# WP75xx_2_no_usb_v.net
KiCad netlist of a schematic drawn in EAGLE
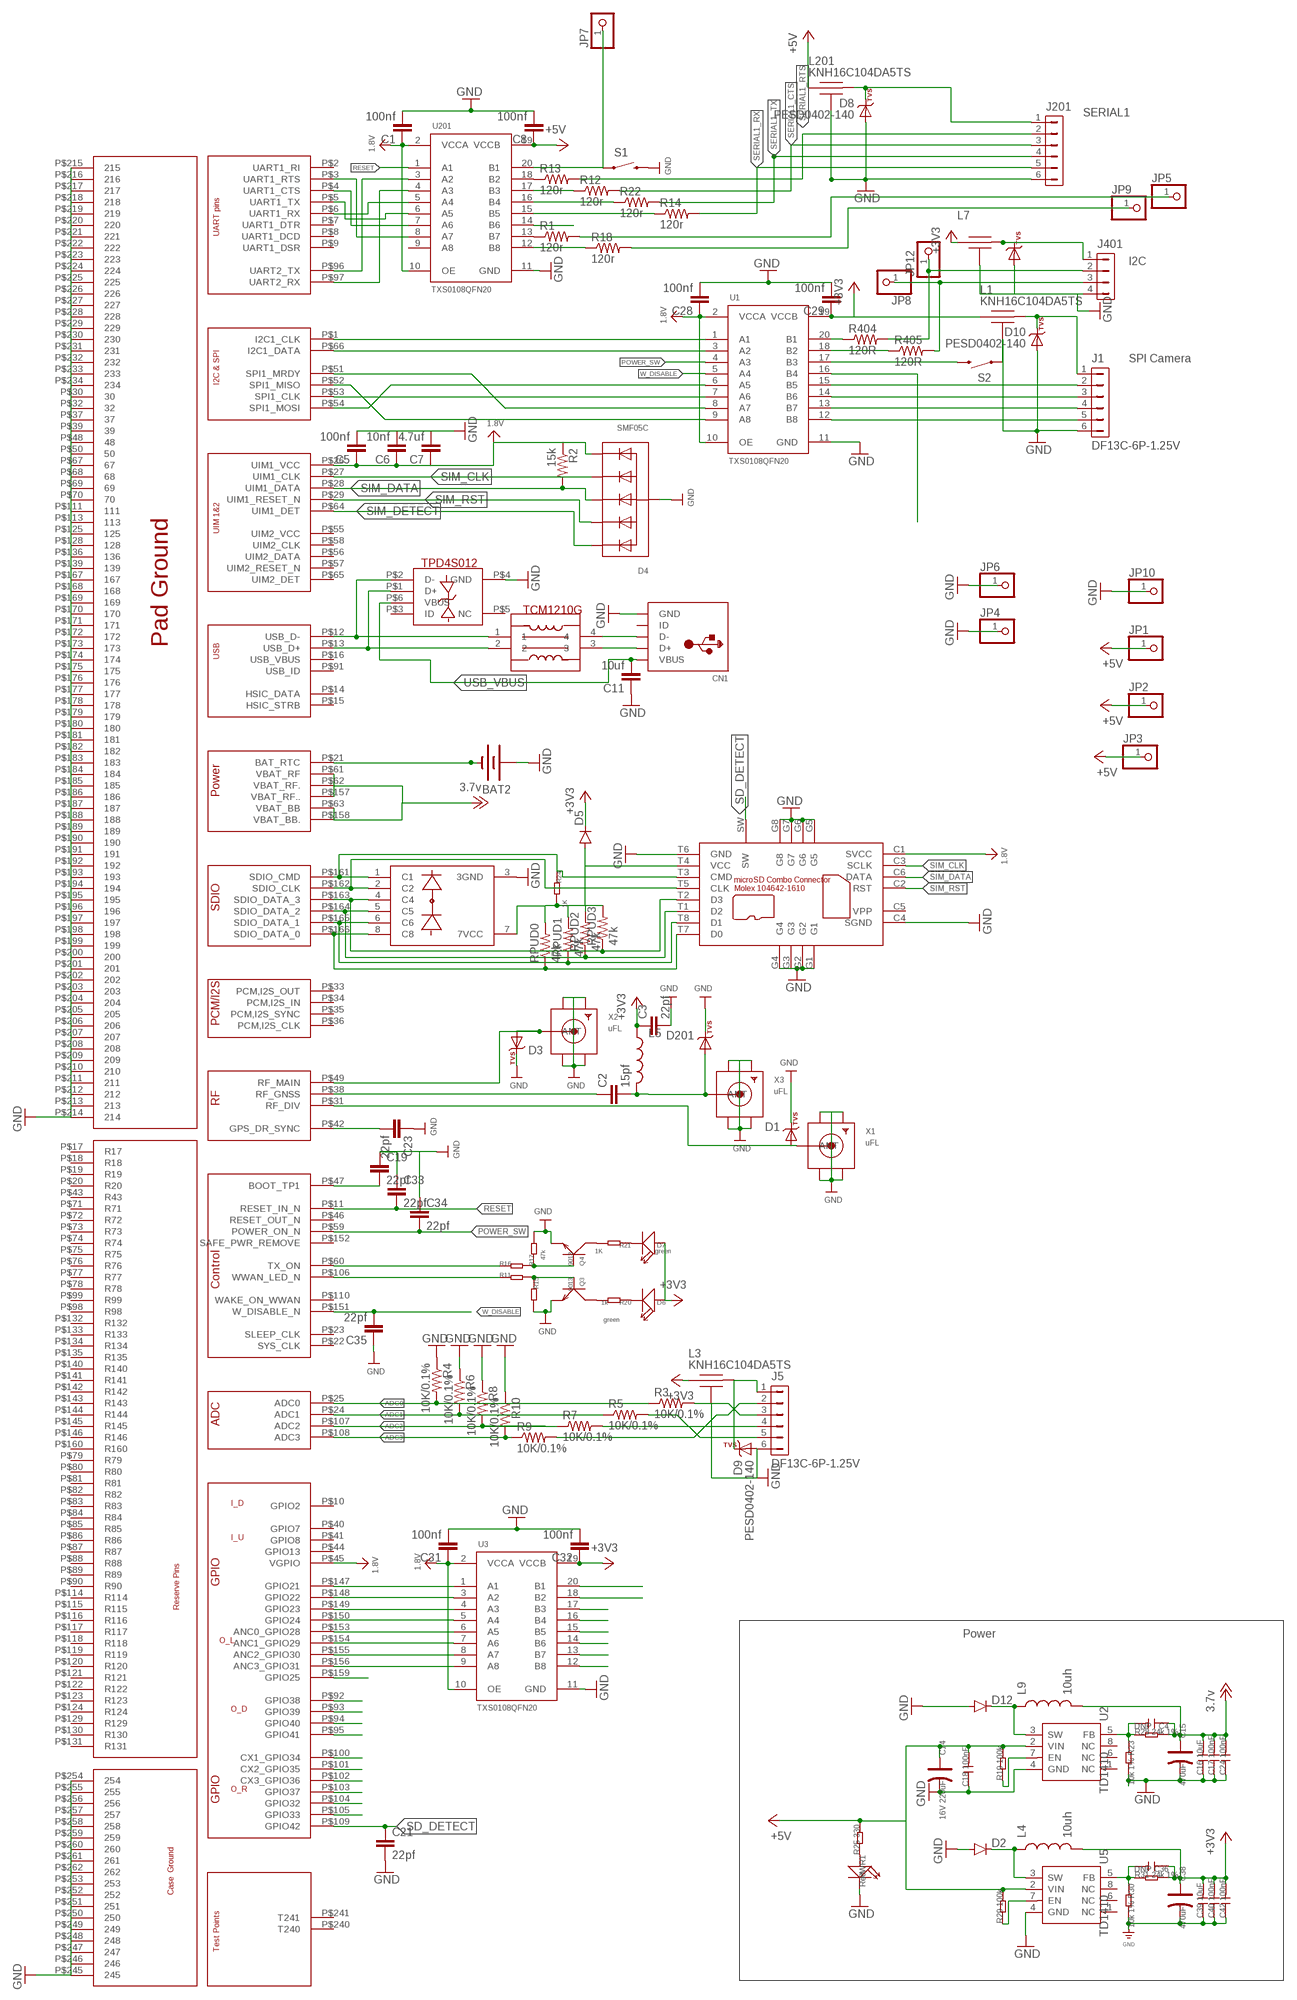
[diagram p0: schematic, sheet 1]

(export (version "E")
  (design (tool "Eeschema 10.0.6"))
  (components
    (comp (ref "BAT2")
      (value "BATTERY12MM")
      (footprint "eagle-import:BATTCON_12MM")
      (libsource (lib "eagle-import") (part "BATTERY12MM"))
    )
    (comp (ref "C1")
      (value "100nf")
      (footprint "eagle-import:0805-CAP")
      (libsource (lib "eagle-import") (part "1.0UF-25V-+80/-20(0805){dblquote}"))
    )
    (comp (ref "C2")
      (value "15pf")
      (footprint "eagle-import:0603-CAP")
      (libsource (lib "eagle-import") (part "0.1UF-25V(+80/-20%)(0603)"))
    )
    (comp (ref "C3")
      (value "22pf")
      (footprint "eagle-import:0603-CAP")
      (libsource (lib "eagle-import") (part "0.1UF-25V(+80/-20%)(0603)"))
    )
    (comp (ref "C4")
      (value "DNP")
      (footprint "eagle-import:C0603")
      (libsource (lib "eagle-import") (part "C-0603"))
    )
    (comp (ref "C5")
      (value "100nf")
      (footprint "eagle-import:0805-CAP")
      (libsource (lib "eagle-import") (part "1.0UF-25V-+80/-20(0805){dblquote}"))
    )
    (comp (ref "C6")
      (value "10nf")
      (footprint "eagle-import:0805-CAP")
      (libsource (lib "eagle-import") (part "1.0UF-25V-+80/-20(0805){dblquote}"))
    )
    (comp (ref "C7")
      (value "4.7uf")
      (footprint "eagle-import:0805-CAP")
      (libsource (lib "eagle-import") (part "1.0UF-25V-+80/-20(0805){dblquote}"))
    )
    (comp (ref "C8")
      (value "100nf")
      (footprint "eagle-import:0805-CAP")
      (libsource (lib "eagle-import") (part "1.0UF-25V-+80/-20(0805){dblquote}"))
    )
    (comp (ref "C11")
      (value "10uf")
      (footprint "eagle-import:0603-CAP")
      (libsource (lib "eagle-import") (part "0.1UF-25V(+80/-20%)(0603)"))
    )
    (comp (ref "C14")
      (value "16V 220uF")
      (footprint "eagle-import:ELECTRO-SMD-D-5.6MM")
      (libsource (lib "eagle-import") (part "CAP-ELECTRO-D"))
    )
    (comp (ref "C15")
      (value "470uF")
      (footprint "eagle-import:AVX-D")
      (libsource (lib "eagle-import") (part "CAP-AVX-D"))
    )
    (comp (ref "C16")
      (value "10uF")
      (footprint "eagle-import:C0805")
      (libsource (lib "eagle-import") (part "C-0805"))
    )
    (comp (ref "C17")
      (value "100nF")
      (footprint "eagle-import:C0603")
      (libsource (lib "eagle-import") (part "C-0603"))
    )
    (comp (ref "C18")
      (value "100nF")
      (footprint "eagle-import:C0603")
      (libsource (lib "eagle-import") (part "C-0603"))
    )
    (comp (ref "C19")
      (value "22pf")
      (footprint "eagle-import:0603-CAP")
      (libsource (lib "eagle-import") (part "0.1UF-25V(+80/-20%)(0603)"))
    )
    (comp (ref "C21")
      (value "22pf")
      (footprint "eagle-import:0603-CAP")
      (libsource (lib "eagle-import") (part "0.1UF-25V(+80/-20%)(0603)"))
    )
    (comp (ref "C23")
      (value "22pf")
      (footprint "eagle-import:0603-CAP")
      (libsource (lib "eagle-import") (part "0.1UF-25V(+80/-20%)(0603)"))
    )
    (comp (ref "C24")
      (value "100nF")
      (footprint "eagle-import:C0603")
      (libsource (lib "eagle-import") (part "C-0603"))
    )
    (comp (ref "C28")
      (value "100nf")
      (footprint "eagle-import:0805-CAP")
      (libsource (lib "eagle-import") (part "1.0UF-25V-+80/-20(0805){dblquote}"))
    )
    (comp (ref "C29")
      (value "100nf")
      (footprint "eagle-import:0805-CAP")
      (libsource (lib "eagle-import") (part "1.0UF-25V-+80/-20(0805){dblquote}"))
    )
    (comp (ref "C31")
      (value "100nf")
      (footprint "eagle-import:0805-CAP")
      (libsource (lib "eagle-import") (part "1.0UF-25V-+80/-20(0805){dblquote}"))
    )
    (comp (ref "C32")
      (value "100nf")
      (footprint "eagle-import:0805-CAP")
      (libsource (lib "eagle-import") (part "1.0UF-25V-+80/-20(0805){dblquote}"))
    )
    (comp (ref "C33")
      (value "22pf")
      (footprint "eagle-import:0603-CAP")
      (libsource (lib "eagle-import") (part "0.1UF-25V(+80/-20%)(0603)"))
    )
    (comp (ref "C34")
      (value "22pf")
      (footprint "eagle-import:0603-CAP")
      (libsource (lib "eagle-import") (part "0.1UF-25V(+80/-20%)(0603)"))
    )
    (comp (ref "C35")
      (value "22pf")
      (footprint "eagle-import:0603-CAP")
      (libsource (lib "eagle-import") (part "0.1UF-25V(+80/-20%)(0603)"))
    )
    (comp (ref "C36")
      (value "DNP")
      (footprint "eagle-import:C0603")
      (libsource (lib "eagle-import") (part "C-0603"))
    )
    (comp (ref "C38")
      (value "470uF")
      (footprint "eagle-import:AVX-D")
      (libsource (lib "eagle-import") (part "CAP-AVX-D"))
    )
    (comp (ref "C39")
      (value "10uF")
      (footprint "eagle-import:C0805")
      (libsource (lib "eagle-import") (part "C-0805"))
    )
    (comp (ref "C40")
      (value "100nF")
      (footprint "eagle-import:C0603")
      (libsource (lib "eagle-import") (part "C-0603"))
    )
    (comp (ref "C42")
      (value "100nF")
      (footprint "eagle-import:C0603")
      (libsource (lib "eagle-import") (part "C-0603"))
    )
    (comp (ref "CN1")
      (value "USBMINIB")
      (footprint "eagle-import:USB-MINIB")
      (libsource (lib "eagle-import") (part "USBMINIB"))
    )
    (comp (ref "D1")
      (value "DIODE-TVS")
      (footprint "eagle-import:0402-TVS")
      (fields (field (name "PARTNO") "PESD0402-140"))
      (libsource (lib "eagle-import") (part "DIODE-TVS"))
    )
    (comp (ref "D2")
      (value "DIODESMA-KIT")
      (footprint "eagle-import:SMA-DIODE-KIT")
      (libsource (lib "eagle-import") (part "DIODESMA-KIT"))
    )
    (comp (ref "D3")
      (value "DIODE-TVS")
      (footprint "eagle-import:0402-TVS")
      (fields (field (name "PARTNO") "PESD0402-140"))
      (libsource (lib "eagle-import") (part "DIODE-TVS"))
    )
    (comp (ref "D4")
      (value "SMF05C")
      (footprint "eagle-import:SOT363")
      (libsource (lib "eagle-import") (part "TVSARRAY_5LANE"))
    )
    (comp (ref "D5")
      (value "DIODESOD123")
      (footprint "eagle-import:SOD-123")
      (libsource (lib "eagle-import") (part "DIODESOD123"))
    )
    (comp (ref "D6")
      (value "green")
      (footprint "eagle-import:LED-0603")
      (libsource (lib "eagle-import") (part "LED'0603'"))
    )
    (comp (ref "D7")
      (value "green")
      (footprint "eagle-import:LED-0603")
      (libsource (lib "eagle-import") (part "LED'0603'"))
    )
    (comp (ref "D8")
      (value "PESD0402-140")
      (footprint "eagle-import:0402-TVS")
      (libsource (lib "eagle-import") (part "DIODE-TVS"))
    )
    (comp (ref "D9")
      (value "PESD0402-140")
      (footprint "eagle-import:0402-TVS")
      (libsource (lib "eagle-import") (part "DIODE-TVS"))
    )
    (comp (ref "D10")
      (value "PESD0402-140")
      (footprint "eagle-import:0402-TVS")
      (libsource (lib "eagle-import") (part "DIODE-TVS"))
    )
    (comp (ref "D12")
      (value "DIODESMA-KIT")
      (footprint "eagle-import:SMA-DIODE-KIT")
      (libsource (lib "eagle-import") (part "DIODESMA-KIT"))
    )
    (comp (ref "D201")
      (value "DIODE-TVS")
      (footprint "eagle-import:0402-TVS")
      (fields (field (name "PARTNO") "PESD0402-140"))
      (libsource (lib "eagle-import") (part "DIODE-TVS"))
    )
    (comp (ref "D401")
      (value "DIODE-TVS")
      (footprint "eagle-import:0402-TVS")
      (fields (field (name "PARTNO") "PESD0402-140"))
      (libsource (lib "eagle-import") (part "DIODE-TVS"))
    )
    (comp (ref "J1")
      (value "DF13C-6P-1.25V")
      (footprint "eagle-import:DF13C-6P-1.25V")
      (fields (field (name "PARTNO") "DF13C-6P-1.25V(20)"))
      (libsource (lib "eagle-import") (part "DF13-6P-1.25V"))
    )
    (comp (ref "J5")
      (value "DF13C-6P-1.25V")
      (footprint "eagle-import:DF13C-6P-1.25V")
      (fields (field (name "PARTNO") "DF13C-6P-1.25V(20)"))
      (libsource (lib "eagle-import") (part "DF13-6P-1.25V"))
    )
    (comp (ref "J201")
      (value "DF13-6P-1.25V")
      (footprint "eagle-import:DF13C-6P-1.25V")
      (fields (field (name "PARTNO") "DF13C-6P-1.25V(20)"))
      (libsource (lib "eagle-import") (part "DF13-6P-1.25V"))
    )
    (comp (ref "J401")
      (value "DF13-4P-1.25V")
      (footprint "eagle-import:DF13C-4P-1.25V")
      (fields (field (name "PARTNO") "DF13C-4P-1.25V(20)"))
      (libsource (lib "eagle-import") (part "DF13-4P-1.25V"))
    )
    (comp (ref "JP1")
      (value "PINHD-1X1")
      (footprint "eagle-import:1X01")
      (libsource (lib "eagle-import") (part "PINHD-1X1"))
    )
    (comp (ref "JP2")
      (value "PINHD-1X1")
      (footprint "eagle-import:1X01")
      (libsource (lib "eagle-import") (part "PINHD-1X1"))
    )
    (comp (ref "JP3")
      (value "PINHD-1X1")
      (footprint "eagle-import:1X01")
      (libsource (lib "eagle-import") (part "PINHD-1X1"))
    )
    (comp (ref "JP4")
      (value "PINHD-1X1")
      (footprint "eagle-import:1X01")
      (libsource (lib "eagle-import") (part "PINHD-1X1"))
    )
    (comp (ref "JP5")
      (value "PINHD-1X1")
      (footprint "eagle-import:1X01")
      (libsource (lib "eagle-import") (part "PINHD-1X1"))
    )
    (comp (ref "JP6")
      (value "PINHD-1X1")
      (footprint "eagle-import:1X01")
      (libsource (lib "eagle-import") (part "PINHD-1X1"))
    )
    (comp (ref "JP7")
      (value "PINHD-1X1")
      (footprint "eagle-import:1X01")
      (libsource (lib "eagle-import") (part "PINHD-1X1"))
    )
    (comp (ref "JP8")
      (value "PINHD-1X1")
      (footprint "eagle-import:1X01")
      (libsource (lib "eagle-import") (part "PINHD-1X1"))
    )
    (comp (ref "JP9")
      (value "PINHD-1X1")
      (footprint "eagle-import:1X01")
      (libsource (lib "eagle-import") (part "PINHD-1X1"))
    )
    (comp (ref "JP10")
      (value "PINHD-1X1")
      (footprint "eagle-import:1X01")
      (libsource (lib "eagle-import") (part "PINHD-1X1"))
    )
    (comp (ref "JP12")
      (value "PINHD-1X1")
      (footprint "eagle-import:1X01")
      (libsource (lib "eagle-import") (part "PINHD-1X1"))
    )
    (comp (ref "L1")
      (value "KNH16C104DA5TS")
      (footprint "eagle-import:KYOCERA-KNH16-DA")
      (libsource (lib "eagle-import") (part "KNH16C104DA5TS"))
    )
    (comp (ref "L3")
      (value "KNH16C104DA5TS")
      (footprint "eagle-import:KYOCERA-KNH16-DA")
      (libsource (lib "eagle-import") (part "KNH16C104DA5TS"))
    )
    (comp (ref "L4")
      (value "10uh")
      (footprint "eagle-import:1210")
      (libsource (lib "eagle-import") (part "INDUCTOR1210"))
    )
    (comp (ref "L5")
      (value "INDUCTOR30OHM,1.8A")
      (footprint "eagle-import:0603")
      (libsource (lib "eagle-import") (part "INDUCTOR30OHM,1.8A"))
    )
    (comp (ref "L7")
      (value "KNH16C104DA5TS")
      (footprint "eagle-import:KYOCERA-KNH16-DA")
      (libsource (lib "eagle-import") (part "KNH16C104DA5TS"))
    )
    (comp (ref "L9")
      (value "10uh")
      (footprint "eagle-import:1210")
      (libsource (lib "eagle-import") (part "INDUCTOR1210"))
    )
    (comp (ref "L201")
      (value "KNH16C104DA5TS")
      (footprint "eagle-import:KYOCERA-KNH16-DA")
      (libsource (lib "eagle-import") (part "KNH16C104DA5TS"))
    )
    (comp (ref "PWR1")
      (value "Red")
      (footprint "eagle-import:D0603")
      (libsource (lib "eagle-import") (part "007-LED0603"))
    )
    (comp (ref "Q3")
      (value "9013")
      (footprint "eagle-import:SOT23")
      (libsource (lib "eagle-import") (part "TRANSISTOR-NPN-SOT23"))
    )
    (comp (ref "Q4")
      (value "9013")
      (footprint "eagle-import:SOT23")
      (libsource (lib "eagle-import") (part "TRANSISTOR-NPN-SOT23"))
    )
    (comp (ref "R1")
      (value "120r")
      (footprint "eagle-import:0603")
      (libsource (lib "eagle-import") (part "0.05OHM-1/5W-1%(0603)"))
    )
    (comp (ref "R2")
      (value "15k")
      (footprint "eagle-import:0603")
      (libsource (lib "eagle-import") (part "0.05OHM-1/5W-1%(0603)"))
    )
    (comp (ref "R3")
      (value "10K/0.1%")
      (footprint "eagle-import:0402-RES")
      (fields (field (name "PARTNO") "ERA-2AEB103X"))
      (libsource (lib "eagle-import") (part "RESISTOR0402-RES"))
    )
    (comp (ref "R4")
      (value "10K/0.1%")
      (footprint "eagle-import:0402-RES")
      (fields (field (name "PARTNO") "ERA-2AEB103X"))
      (libsource (lib "eagle-import") (part "RESISTOR0402-RES"))
    )
    (comp (ref "R5")
      (value "10K/0.1%")
      (footprint "eagle-import:0402-RES")
      (fields (field (name "PARTNO") "ERA-2AEB103X"))
      (libsource (lib "eagle-import") (part "RESISTOR0402-RES"))
    )
    (comp (ref "R6")
      (value "10K/0.1%")
      (footprint "eagle-import:0402-RES")
      (fields (field (name "PARTNO") "ERA-2AEB103X"))
      (libsource (lib "eagle-import") (part "RESISTOR0402-RES"))
    )
    (comp (ref "R7")
      (value "10K/0.1%")
      (footprint "eagle-import:0402-RES")
      (fields (field (name "PARTNO") "ERA-2AEB103X"))
      (libsource (lib "eagle-import") (part "RESISTOR0402-RES"))
    )
    (comp (ref "R8")
      (value "10K/0.1%")
      (footprint "eagle-import:0402-RES")
      (fields (field (name "PARTNO") "ERA-2AEB103X"))
      (libsource (lib "eagle-import") (part "RESISTOR0402-RES"))
    )
    (comp (ref "R9")
      (value "10K/0.1%")
      (footprint "eagle-import:0402-RES")
      (fields (field (name "PARTNO") "ERA-2AEB103X"))
      (libsource (lib "eagle-import") (part "RESISTOR0402-RES"))
    )
    (comp (ref "R10")
      (value "10K/0.1%")
      (footprint "eagle-import:0402-RES")
      (fields (field (name "PARTNO") "ERA-2AEB103X"))
      (libsource (lib "eagle-import") (part "RESISTOR0402-RES"))
    )
    (comp (ref "R11")
      (value "4.7k")
      (footprint "eagle-import:R0603")
      (libsource (lib "eagle-import") (part "R-0603"))
    )
    (comp (ref "R12")
      (value "120r")
      (footprint "eagle-import:0603")
      (libsource (lib "eagle-import") (part "0.05OHM-1/5W-1%(0603)"))
    )
    (comp (ref "R13")
      (value "120r")
      (footprint "eagle-import:0603")
      (libsource (lib "eagle-import") (part "0.05OHM-1/5W-1%(0603)"))
    )
    (comp (ref "R14")
      (value "120r")
      (footprint "eagle-import:0603")
      (libsource (lib "eagle-import") (part "0.05OHM-1/5W-1%(0603)"))
    )
    (comp (ref "R15")
      (value "47k")
      (footprint "eagle-import:R0603")
      (libsource (lib "eagle-import") (part "R-0603"))
    )
    (comp (ref "R16")
      (value "4.7k")
      (footprint "eagle-import:R0603")
      (libsource (lib "eagle-import") (part "R-0603"))
    )
    (comp (ref "R17")
      (value "47k")
      (footprint "eagle-import:R0603")
      (libsource (lib "eagle-import") (part "R-0603"))
    )
    (comp (ref "R18")
      (value "120r")
      (footprint "eagle-import:0603")
      (libsource (lib "eagle-import") (part "0.05OHM-1/5W-1%(0603)"))
    )
    (comp (ref "R19")
      (value "100k")
      (footprint "eagle-import:R0603")
      (libsource (lib "eagle-import") (part "R-0603"))
    )
    (comp (ref "R20")
      (value "1k")
      (footprint "eagle-import:R0603")
      (libsource (lib "eagle-import") (part "R-0603"))
    )
    (comp (ref "R21")
      (value "1K")
      (footprint "eagle-import:R0603")
      (libsource (lib "eagle-import") (part "R-0603"))
    )
    (comp (ref "R22")
      (value "120r")
      (footprint "eagle-import:0603")
      (libsource (lib "eagle-import") (part "0.05OHM-1/5W-1%(0603)"))
    )
    (comp (ref "R23")
      (value "10k 1%")
      (footprint "eagle-import:R0603")
      (libsource (lib "eagle-import") (part "R-0603"))
    )
    (comp (ref "R24")
      (value "1K")
      (footprint "eagle-import:R0603")
      (libsource (lib "eagle-import") (part "R-0603"))
    )
    (comp (ref "R25")
      (value "330")
      (footprint "eagle-import:R0603")
      (libsource (lib "eagle-import") (part "R-0603"))
    )
    (comp (ref "R28")
      (value "24k 1%")
      (footprint "eagle-import:R0603")
      (libsource (lib "eagle-import") (part "R-0603"))
    )
    (comp (ref "R29")
      (value "100k")
      (footprint "eagle-import:R0603")
      (libsource (lib "eagle-import") (part "R-0603"))
    )
    (comp (ref "R30")
      (value "10k 1%")
      (footprint "eagle-import:R0603")
      (libsource (lib "eagle-import") (part "R-0603"))
    )
    (comp (ref "R31")
      (value "24k 1%")
      (footprint "eagle-import:R0603")
      (libsource (lib "eagle-import") (part "R-0603"))
    )
    (comp (ref "R404")
      (value "120R")
      (footprint "eagle-import:0402-RES")
      (fields (field (name "PARTNO") "RC0402FR-07120RL"))
      (libsource (lib "eagle-import") (part "RESISTOR0402-RES"))
    )
    (comp (ref "R405")
      (value "120R")
      (footprint "eagle-import:0402-RES")
      (fields (field (name "PARTNO") "RC0402FR-07120RL"))
      (libsource (lib "eagle-import") (part "RESISTOR0402-RES"))
    )
    (comp (ref "RPUD0")
      (value "47k")
      (footprint "eagle-import:0603")
      (libsource (lib "eagle-import") (part "0.05OHM-1/5W-1%(0603)"))
    )
    (comp (ref "RPUD1")
      (value "47k")
      (footprint "eagle-import:0603")
      (libsource (lib "eagle-import") (part "0.05OHM-1/5W-1%(0603)"))
    )
    (comp (ref "RPUD2")
      (value "47k")
      (footprint "eagle-import:0603")
      (libsource (lib "eagle-import") (part "0.05OHM-1/5W-1%(0603)"))
    )
    (comp (ref "RPUD3")
      (value "47k")
      (footprint "eagle-import:0603")
      (libsource (lib "eagle-import") (part "0.05OHM-1/5W-1%(0603)"))
    )
    (comp (ref "S1")
      (value "SWITCH-MOMENTARY-2SMD-1101NE")
      (footprint "eagle-import:TACTILE-SWITCH-1101NE")
      (libsource (lib "eagle-import") (part "SWITCH-MOMENTARY-2SMD-1101NE"))
    )
    (comp (ref "S2")
      (value "SWITCH-MOMENTARY-2SMD-1101NE")
      (footprint "eagle-import:TACTILE-SWITCH-1101NE")
      (libsource (lib "eagle-import") (part "SWITCH-MOMENTARY-2SMD-1101NE"))
    )
    (comp (ref "U$1")
      (value "SOCKETY_WP75XXX")
      (footprint "eagle-import:SOCKET_WP75XX")
      (libsource (lib "eagle-import") (part "SOCKETY_WP75XXX"))
    )
    (comp (ref "U$11")
      (value "TCM1210G")
      (footprint "eagle-import:TCM1210G")
      (libsource (lib "eagle-import") (part "TCM1210G"))
    )
    (comp (ref "U$12")
      (value "TPD4S012")
      (footprint "eagle-import:TPD4S012")
      (libsource (lib "eagle-import") (part "TPD4S012"))
    )
    (comp (ref "U$14")
      (value "SD_SIM_M1610")
      (footprint "eagle-import:SIM_SD_HOLDER")
      (libsource (lib "eagle-import") (part "SD_SIM_M1610"))
    )
    (comp (ref "U$15")
      (value "PACDN006")
      (footprint "eagle-import:MSOP8")
      (libsource (lib "eagle-import") (part "PACDN006"))
    )
    (comp (ref "U1")
      (value "TXS0108QFN20")
      (footprint "eagle-import:QFN20-RGY")
      (fields (field (name "PARTNO") "TXS0108ERGYR"))
      (libsource (lib "eagle-import") (part "TXS0108QFN20"))
    )
    (comp (ref "U2")
      (value "TD1410")
      (footprint "eagle-import:SOP8")
      (libsource (lib "eagle-import") (part "TD1410"))
    )
    (comp (ref "U3")
      (value "TXS0108QFN20")
      (footprint "eagle-import:QFN20-RGY")
      (fields (field (name "PARTNO") "TXS0108ERGYR"))
      (libsource (lib "eagle-import") (part "TXS0108QFN20"))
    )
    (comp (ref "U5")
      (value "TD1410")
      (footprint "eagle-import:SOP8")
      (libsource (lib "eagle-import") (part "TD1410"))
    )
    (comp (ref "U201")
      (value "TXS0108QFN20")
      (footprint "eagle-import:QFN20-RGY")
      (fields (field (name "PARTNO") "TXS0108ERGYR"))
      (libsource (lib "eagle-import") (part "TXS0108QFN20"))
    )
    (comp (ref "X1")
      (value "uFL")
      (footprint "eagle-import:SMA_EDGELAUNCH_UFL")
      (libsource (lib "eagle-import") (part "SMACONNECTOR_EDGE_UFL"))
    )
    (comp (ref "X2")
      (value "uFL")
      (footprint "eagle-import:SMA_EDGELAUNCH_UFL")
      (libsource (lib "eagle-import") (part "SMACONNECTOR_EDGE_UFL"))
    )
    (comp (ref "X3")
      (value "uFL")
      (footprint "eagle-import:SMA_EDGELAUNCH_UFL")
      (libsource (lib "eagle-import") (part "SMACONNECTOR_EDGE_UFL"))
    )
  )
  (nets
    (net (code "1") (name "+3V3") (class "Default")
      (node (ref "C29") (pin "1") (pinfunction "1_1") (pintype "passive"))
      (node (ref "C3") (pin "1") (pinfunction "1_1") (pintype "passive"))
      (node (ref "C32") (pin "1") (pinfunction "1_1") (pintype "passive"))
      (node (ref "C36") (pin "1") (pinfunction "1_1") (pintype "passive"))
      (node (ref "C38") (pin "+") (pinfunction "+_+") (pintype "passive"))
      (node (ref "C39") (pin "2") (pinfunction "2_2") (pintype "passive"))
      (node (ref "C40") (pin "2") (pinfunction "2_2") (pintype "passive"))
      (node (ref "C42") (pin "2") (pinfunction "2_2") (pintype "passive"))
      (node (ref "D5") (pin "C") (pinfunction "C_C") (pintype "passive"))
      (node (ref "D6") (pin "+") (pinfunction "+_+") (pintype "passive"))
      (node (ref "D7") (pin "+") (pinfunction "+_+") (pintype "passive"))
      (node (ref "L1") (pin "P$1") (pinfunction "P$1_P$1") (pintype "bidirectional"))
      (node (ref "L3") (pin "P$1") (pinfunction "P$1_P$1") (pintype "bidirectional"))
      (node (ref "L4") (pin "2") (pinfunction "2_2") (pintype "passive"))
      (node (ref "L5") (pin "1") (pinfunction "1_1") (pintype "passive"))
      (node (ref "L7") (pin "P$1") (pinfunction "P$1_P$1") (pintype "bidirectional"))
      (node (ref "R31") (pin "2") (pinfunction "2_2") (pintype "passive"))
      (node (ref "U1") (pin "19") (pinfunction "VCCB_19") (pintype "input"))
      (node (ref "U3") (pin "19") (pinfunction "VCCB_19") (pintype "input"))
    )
    (net (code "2") (name "+5V") (class "Default")
      (node (ref "C14") (pin "+") (pinfunction "+_+") (pintype "passive"))
      (node (ref "C18") (pin "2") (pinfunction "2_2") (pintype "passive"))
      (node (ref "C8") (pin "1") (pinfunction "1_1") (pintype "passive"))
      (node (ref "JP1") (pin "1") (pinfunction "1_1") (pintype "passive"))
      (node (ref "JP2") (pin "1") (pinfunction "1_1") (pintype "passive"))
      (node (ref "JP3") (pin "1") (pinfunction "1_1") (pintype "passive"))
      (node (ref "L201") (pin "P$1") (pinfunction "P$1_P$1") (pintype "bidirectional"))
      (node (ref "R19") (pin "2") (pinfunction "2_2") (pintype "passive"))
      (node (ref "R25") (pin "2") (pinfunction "2_2") (pintype "passive"))
      (node (ref "R29") (pin "2") (pinfunction "2_2") (pintype "passive"))
      (node (ref "U2") (pin "2") (pinfunction "VIN_2") (pintype "input"))
      (node (ref "U201") (pin "19") (pinfunction "VCCB_19") (pintype "input"))
      (node (ref "U5") (pin "2") (pinfunction "VIN_2") (pintype "input"))
    )
    (net (code "3") (name "1.8V") (class "Default")
      (node (ref "C1") (pin "1") (pinfunction "1_1") (pintype "passive"))
      (node (ref "C28") (pin "1") (pinfunction "1_1") (pintype "passive"))
      (node (ref "C31") (pin "1") (pinfunction "1_1") (pintype "passive"))
      (node (ref "C5") (pin "1") (pinfunction "1_1") (pintype "passive"))
      (node (ref "C6") (pin "1") (pinfunction "1_1") (pintype "passive"))
      (node (ref "C7") (pin "1") (pinfunction "1_1") (pintype "passive"))
      (node (ref "D4") (pin "6") (pinfunction "C5_6") (pintype "passive"))
      (node (ref "R2") (pin "1") (pinfunction "1_1") (pintype "passive"))
      (node (ref "U$1") (pin "P$26") (pinfunction "UIM1_VCC_P$26") (pintype "bidirectional"))
      (node (ref "U$1") (pin "P$45") (pinfunction "VGPIO_P$45") (pintype "bidirectional"))
      (node (ref "U$14") (pin "C1") (pinfunction "SVCC_C1") (pintype "bidirectional"))
      (node (ref "U1") (pin "10") (pinfunction "OE_10") (pintype "input"))
      (node (ref "U1") (pin "2") (pinfunction "VCCA_2") (pintype "input"))
      (node (ref "U201") (pin "10") (pinfunction "OE_10") (pintype "input"))
      (node (ref "U201") (pin "2") (pinfunction "VCCA_2") (pintype "input"))
      (node (ref "U3") (pin "10") (pinfunction "OE_10") (pintype "input"))
      (node (ref "U3") (pin "2") (pinfunction "VCCA_2") (pintype "input"))
    )
    (net (code "4") (name "3.7v") (class "Default")
      (node (ref "C15") (pin "+") (pinfunction "+_+") (pintype "passive"))
      (node (ref "C16") (pin "2") (pinfunction "2_2") (pintype "passive"))
      (node (ref "C17") (pin "2") (pinfunction "2_2") (pintype "passive"))
      (node (ref "C24") (pin "2") (pinfunction "2_2") (pintype "passive"))
      (node (ref "C4") (pin "1") (pinfunction "1_1") (pintype "passive"))
      (node (ref "L9") (pin "2") (pinfunction "2_2") (pintype "passive"))
      (node (ref "R28") (pin "2") (pinfunction "2_2") (pintype "passive"))
      (node (ref "U$1") (pin "P$157") (pinfunction "VBAT_RF.._P$157") (pintype "bidirectional"))
      (node (ref "U$1") (pin "P$158") (pinfunction "VBAT_BB._P$158") (pintype "bidirectional"))
      (node (ref "U$1") (pin "P$61") (pinfunction "VBAT_RF_P$61") (pintype "bidirectional"))
      (node (ref "U$1") (pin "P$62") (pinfunction "VBAT_RF._P$62") (pintype "bidirectional"))
      (node (ref "U$1") (pin "P$63") (pinfunction "VBAT_BB_P$63") (pintype "bidirectional"))
    )
    (net (code "5") (name "ADC0") (class "Default")
      (node (ref "R3") (pin "P$1") (pinfunction "1_P$1") (pintype "passive"))
      (node (ref "R4") (pin "P$2") (pinfunction "2_P$2") (pintype "passive"))
      (node (ref "U$1") (pin "P$25") (pinfunction "ADC0_P$25") (pintype "bidirectional"))
    )
    (net (code "6") (name "ADC1") (class "Default")
      (node (ref "R5") (pin "P$1") (pinfunction "1_P$1") (pintype "passive"))
      (node (ref "R6") (pin "P$2") (pinfunction "2_P$2") (pintype "passive"))
      (node (ref "U$1") (pin "P$24") (pinfunction "ADC1_P$24") (pintype "bidirectional"))
    )
    (net (code "7") (name "ADC2") (class "Default")
      (node (ref "R7") (pin "P$1") (pinfunction "1_P$1") (pintype "passive"))
      (node (ref "R8") (pin "P$2") (pinfunction "2_P$2") (pintype "passive"))
      (node (ref "U$1") (pin "P$107") (pinfunction "ADC2_P$107") (pintype "bidirectional"))
    )
    (net (code "8") (name "ADC3") (class "Default")
      (node (ref "R10") (pin "P$2") (pinfunction "2_P$2") (pintype "passive"))
      (node (ref "R9") (pin "P$1") (pinfunction "1_P$1") (pintype "passive"))
      (node (ref "U$1") (pin "P$108") (pinfunction "ADC3_P$108") (pintype "bidirectional"))
    )
    (net (code "9") (name "GND") (class "Default")
      (node (ref "BAT2") (pin "PWR@1") (pinfunction "+_PWR@1") (pintype "power_in"))
      (node (ref "C1") (pin "2") (pinfunction "2_2") (pintype "passive"))
      (node (ref "C11") (pin "1") (pinfunction "1_1") (pintype "passive"))
      (node (ref "C14") (pin "-") (pinfunction "-_-") (pintype "passive"))
      (node (ref "C15") (pin "-") (pinfunction "-_-") (pintype "passive"))
      (node (ref "C16") (pin "1") (pinfunction "1_1") (pintype "passive"))
      (node (ref "C17") (pin "1") (pinfunction "1_1") (pintype "passive"))
      (node (ref "C18") (pin "1") (pinfunction "1_1") (pintype "passive"))
      (node (ref "C19") (pin "1") (pinfunction "1_1") (pintype "passive"))
      (node (ref "C21") (pin "2") (pinfunction "2_2") (pintype "passive"))
      (node (ref "C23") (pin "1") (pinfunction "1_1") (pintype "passive"))
      (node (ref "C24") (pin "1") (pinfunction "1_1") (pintype "passive"))
      (node (ref "C28") (pin "2") (pinfunction "2_2") (pintype "passive"))
      (node (ref "C29") (pin "2") (pinfunction "2_2") (pintype "passive"))
      (node (ref "C3") (pin "2") (pinfunction "2_2") (pintype "passive"))
      (node (ref "C31") (pin "2") (pinfunction "2_2") (pintype "passive"))
      (node (ref "C32") (pin "2") (pinfunction "2_2") (pintype "passive"))
      (node (ref "C33") (pin "1") (pinfunction "1_1") (pintype "passive"))
      (node (ref "C34") (pin "1") (pinfunction "1_1") (pintype "passive"))
      (node (ref "C35") (pin "1") (pinfunction "1_1") (pintype "passive"))
      (node (ref "C38") (pin "-") (pinfunction "-_-") (pintype "passive"))
      (node (ref "C39") (pin "1") (pinfunction "1_1") (pintype "passive"))
      (node (ref "C40") (pin "1") (pinfunction "1_1") (pintype "passive"))
      (node (ref "C42") (pin "1") (pinfunction "1_1") (pintype "passive"))
      (node (ref "C5") (pin "2") (pinfunction "2_2") (pintype "passive"))
      (node (ref "C6") (pin "2") (pinfunction "2_2") (pintype "passive"))
      (node (ref "C7") (pin "2") (pinfunction "2_2") (pintype "passive"))
      (node (ref "C8") (pin "2") (pinfunction "2_2") (pintype "passive"))
      (node (ref "CN1") (pin "GND") (pinfunction "GND_GND") (pintype "power_in"))
      (node (ref "D1") (pin "C") (pinfunction "C_C") (pintype "passive"))
      (node (ref "D10") (pin "A") (pinfunction "A_A") (pintype "passive"))
      (node (ref "D12") (pin "A") (pinfunction "A_A") (pintype "passive"))
      (node (ref "D2") (pin "A") (pinfunction "A_A") (pintype "passive"))
      (node (ref "D201") (pin "C") (pinfunction "C_C") (pintype "passive"))
      (node (ref "D3") (pin "C") (pinfunction "C_C") (pintype "passive"))
      (node (ref "D4") (pin "2") (pinfunction "A_2") (pintype "passive"))
      (node (ref "D401") (pin "A") (pinfunction "A_A") (pintype "passive"))
      (node (ref "D8") (pin "A") (pinfunction "A_A") (pintype "passive"))
      (node (ref "D9") (pin "A") (pinfunction "A_A") (pintype "passive"))
      (node (ref "J1") (pin "6") (pinfunction "6_6") (pintype "passive"))
      (node (ref "J201") (pin "6") (pinfunction "6_6") (pintype "passive"))
      (node (ref "J401") (pin "4") (pinfunction "4_4") (pintype "passive"))
      (node (ref "J5") (pin "6") (pinfunction "6_6") (pintype "passive"))
      (node (ref "JP10") (pin "1") (pinfunction "1_1") (pintype "passive"))
      (node (ref "JP4") (pin "1") (pinfunction "1_1") (pintype "passive"))
      (node (ref "JP6") (pin "1") (pinfunction "1_1") (pintype "passive"))
      (node (ref "L1") (pin "P$3") (pinfunction "P$3_P$3") (pintype "bidirectional"))
      (node (ref "L1") (pin "P$4") (pinfunction "P$3_P$4") (pintype "bidirectional"))
      (node (ref "L1") (pin "P$5") (pinfunction "P$3_P$5") (pintype "bidirectional"))
      (node (ref "L201") (pin "P$3") (pinfunction "P$3_P$3") (pintype "bidirectional"))
      (node (ref "L201") (pin "P$4") (pinfunction "P$3_P$4") (pintype "bidirectional"))
      (node (ref "L201") (pin "P$5") (pinfunction "P$3_P$5") (pintype "bidirectional"))
      (node (ref "L3") (pin "P$3") (pinfunction "P$3_P$3") (pintype "bidirectional"))
      (node (ref "L3") (pin "P$4") (pinfunction "P$3_P$4") (pintype "bidirectional"))
      (node (ref "L3") (pin "P$5") (pinfunction "P$3_P$5") (pintype "bidirectional"))
      (node (ref "L7") (pin "P$3") (pinfunction "P$3_P$3") (pintype "bidirectional"))
      (node (ref "L7") (pin "P$4") (pinfunction "P$3_P$4") (pintype "bidirectional"))
      (node (ref "L7") (pin "P$5") (pinfunction "P$3_P$5") (pintype "bidirectional"))
      (node (ref "PWR1") (pin "-") (pinfunction "-_-") (pintype "passive"))
      (node (ref "Q3") (pin "2") (pinfunction "E_2") (pintype "passive"))
      (node (ref "Q4") (pin "2") (pinfunction "E_2") (pintype "passive"))
      (node (ref "R10") (pin "P$1") (pinfunction "1_P$1") (pintype "passive"))
      (node (ref "R15") (pin "2") (pinfunction "2_2") (pintype "passive"))
      (node (ref "R17") (pin "2") (pinfunction "2_2") (pintype "passive"))
      (node (ref "R23") (pin "2") (pinfunction "2_2") (pintype "passive"))
      (node (ref "R30") (pin "2") (pinfunction "2_2") (pintype "passive"))
      (node (ref "R4") (pin "P$1") (pinfunction "1_P$1") (pintype "passive"))
      (node (ref "R6") (pin "P$1") (pinfunction "1_P$1") (pintype "passive"))
      (node (ref "R8") (pin "P$1") (pinfunction "1_P$1") (pintype "passive"))
      (node (ref "S1") (pin "2") (pinfunction "2_2") (pintype "passive"))
      (node (ref "S2") (pin "1") (pinfunction "1_1") (pintype "passive"))
      (node (ref "U$1") (pin "P$111") (pinfunction "111_P$111") (pintype "bidirectional"))
      (node (ref "U$1") (pin "P$113") (pinfunction "113_P$113") (pintype "bidirectional"))
      (node (ref "U$1") (pin "P$125") (pinfunction "125_P$125") (pintype "bidirectional"))
      (node (ref "U$1") (pin "P$128") (pinfunction "128_P$128") (pintype "bidirectional"))
      (node (ref "U$1") (pin "P$136") (pinfunction "136_P$136") (pintype "bidirectional"))
      (node (ref "U$1") (pin "P$139") (pinfunction "139_P$139") (pintype "bidirectional"))
      (node (ref "U$1") (pin "P$167") (pinfunction "167_P$167") (pintype "bidirectional"))
      (node (ref "U$1") (pin "P$168") (pinfunction "168_P$168") (pintype "bidirectional"))
      (node (ref "U$1") (pin "P$169") (pinfunction "169_P$169") (pintype "bidirectional"))
      (node (ref "U$1") (pin "P$170") (pinfunction "170_P$170") (pintype "bidirectional"))
      (node (ref "U$1") (pin "P$171") (pinfunction "171_P$171") (pintype "bidirectional"))
      (node (ref "U$1") (pin "P$172") (pinfunction "172_P$172") (pintype "bidirectional"))
      (node (ref "U$1") (pin "P$173") (pinfunction "173_P$173") (pintype "bidirectional"))
      (node (ref "U$1") (pin "P$174") (pinfunction "174_P$174") (pintype "bidirectional"))
      (node (ref "U$1") (pin "P$175") (pinfunction "175_P$175") (pintype "bidirectional"))
      (node (ref "U$1") (pin "P$176") (pinfunction "176_P$176") (pintype "bidirectional"))
      (node (ref "U$1") (pin "P$177") (pinfunction "177_P$177") (pintype "bidirectional"))
      (node (ref "U$1") (pin "P$178") (pinfunction "178_P$178") (pintype "bidirectional"))
      (node (ref "U$1") (pin "P$179") (pinfunction "179_P$179") (pintype "bidirectional"))
      (node (ref "U$1") (pin "P$180") (pinfunction "180_P$180") (pintype "bidirectional"))
      (node (ref "U$1") (pin "P$181") (pinfunction "181_P$181") (pintype "bidirectional"))
      (node (ref "U$1") (pin "P$182") (pinfunction "182_P$182") (pintype "bidirectional"))
      (node (ref "U$1") (pin "P$183") (pinfunction "183_P$183") (pintype "bidirectional"))
      (node (ref "U$1") (pin "P$184") (pinfunction "184_P$184") (pintype "bidirectional"))
      (node (ref "U$1") (pin "P$185") (pinfunction "185_P$185") (pintype "bidirectional"))
      (node (ref "U$1") (pin "P$186") (pinfunction "186_P$186") (pintype "bidirectional"))
      (node (ref "U$1") (pin "P$187") (pinfunction "187_P$187") (pintype "bidirectional"))
      (node (ref "U$1") (pin "P$188") (pinfunction "188_P$188") (pintype "bidirectional"))
      (node (ref "U$1") (pin "P$189") (pinfunction "189_P$189") (pintype "bidirectional"))
      (node (ref "U$1") (pin "P$190") (pinfunction "190_P$190") (pintype "bidirectional"))
      (node (ref "U$1") (pin "P$191") (pinfunction "191_P$191") (pintype "bidirectional"))
      (node (ref "U$1") (pin "P$192") (pinfunction "192_P$192") (pintype "bidirectional"))
      (node (ref "U$1") (pin "P$193") (pinfunction "193_P$193") (pintype "bidirectional"))
      (node (ref "U$1") (pin "P$194") (pinfunction "194_P$194") (pintype "bidirectional"))
      (node (ref "U$1") (pin "P$195") (pinfunction "195_P$195") (pintype "bidirectional"))
      (node (ref "U$1") (pin "P$196") (pinfunction "196_P$196") (pintype "bidirectional"))
      (node (ref "U$1") (pin "P$197") (pinfunction "197_P$197") (pintype "bidirectional"))
      (node (ref "U$1") (pin "P$198") (pinfunction "198_P$198") (pintype "bidirectional"))
      (node (ref "U$1") (pin "P$199") (pinfunction "199_P$199") (pintype "bidirectional"))
      (node (ref "U$1") (pin "P$200") (pinfunction "200_P$200") (pintype "bidirectional"))
      (node (ref "U$1") (pin "P$201") (pinfunction "201_P$201") (pintype "bidirectional"))
      (node (ref "U$1") (pin "P$202") (pinfunction "202_P$202") (pintype "bidirectional"))
      (node (ref "U$1") (pin "P$203") (pinfunction "203_P$203") (pintype "bidirectional"))
      (node (ref "U$1") (pin "P$204") (pinfunction "204_P$204") (pintype "bidirectional"))
      (node (ref "U$1") (pin "P$205") (pinfunction "205_P$205") (pintype "bidirectional"))
      (node (ref "U$1") (pin "P$206") (pinfunction "206_P$206") (pintype "bidirectional"))
      (node (ref "U$1") (pin "P$207") (pinfunction "207_P$207") (pintype "bidirectional"))
      (node (ref "U$1") (pin "P$208") (pinfunction "208_P$208") (pintype "bidirectional"))
      (node (ref "U$1") (pin "P$209") (pinfunction "209_P$209") (pintype "bidirectional"))
      (node (ref "U$1") (pin "P$210") (pinfunction "210_P$210") (pintype "bidirectional"))
      (node (ref "U$1") (pin "P$211") (pinfunction "211_P$211") (pintype "bidirectional"))
      (node (ref "U$1") (pin "P$212") (pinfunction "212_P$212") (pintype "bidirectional"))
      (node (ref "U$1") (pin "P$213") (pinfunction "213_P$213") (pintype "bidirectional"))
      (node (ref "U$1") (pin "P$214") (pinfunction "214_P$214") (pintype "bidirectional"))
      (node (ref "U$1") (pin "P$215") (pinfunction "215_P$215") (pintype "bidirectional"))
      (node (ref "U$1") (pin "P$216") (pinfunction "216_P$216") (pintype "bidirectional"))
      (node (ref "U$1") (pin "P$217") (pinfunction "217_P$217") (pintype "bidirectional"))
      (node (ref "U$1") (pin "P$218") (pinfunction "218_P$218") (pintype "bidirectional"))
      (node (ref "U$1") (pin "P$219") (pinfunction "219_P$219") (pintype "bidirectional"))
      (node (ref "U$1") (pin "P$220") (pinfunction "220_P$220") (pintype "bidirectional"))
      (node (ref "U$1") (pin "P$221") (pinfunction "221_P$221") (pintype "bidirectional"))
      (node (ref "U$1") (pin "P$222") (pinfunction "222_P$222") (pintype "bidirectional"))
      (node (ref "U$1") (pin "P$223") (pinfunction "223_P$223") (pintype "bidirectional"))
      (node (ref "U$1") (pin "P$224") (pinfunction "224_P$224") (pintype "bidirectional"))
      (node (ref "U$1") (pin "P$225") (pinfunction "225_P$225") (pintype "bidirectional"))
      (node (ref "U$1") (pin "P$226") (pinfunction "226_P$226") (pintype "bidirectional"))
      (node (ref "U$1") (pin "P$227") (pinfunction "227_P$227") (pintype "bidirectional"))
      (node (ref "U$1") (pin "P$228") (pinfunction "228_P$228") (pintype "bidirectional"))
      (node (ref "U$1") (pin "P$229") (pinfunction "229_P$229") (pintype "bidirectional"))
      (node (ref "U$1") (pin "P$230") (pinfunction "230_P$230") (pintype "bidirectional"))
      (node (ref "U$1") (pin "P$231") (pinfunction "231_P$231") (pintype "bidirectional"))
      (node (ref "U$1") (pin "P$232") (pinfunction "232_P$232") (pintype "bidirectional"))
      (node (ref "U$1") (pin "P$233") (pinfunction "233_P$233") (pintype "bidirectional"))
      (node (ref "U$1") (pin "P$234") (pinfunction "234_P$234") (pintype "bidirectional"))
      (node (ref "U$1") (pin "P$245") (pinfunction "245_P$245") (pintype "bidirectional"))
      (node (ref "U$1") (pin "P$246") (pinfunction "246_P$246") (pintype "bidirectional"))
      (node (ref "U$1") (pin "P$247") (pinfunction "247_P$247") (pintype "bidirectional"))
      (node (ref "U$1") (pin "P$248") (pinfunction "248_P$248") (pintype "bidirectional"))
      (node (ref "U$1") (pin "P$249") (pinfunction "249_P$249") (pintype "bidirectional"))
      (node (ref "U$1") (pin "P$250") (pinfunction "250_P$250") (pintype "bidirectional"))
      (node (ref "U$1") (pin "P$251") (pinfunction "251_P$251") (pintype "bidirectional"))
      (node (ref "U$1") (pin "P$252") (pinfunction "252_P$252") (pintype "bidirectional"))
      (node (ref "U$1") (pin "P$253") (pinfunction "253_P$253") (pintype "bidirectional"))
      (node (ref "U$1") (pin "P$254") (pinfunction "254_P$254") (pintype "bidirectional"))
      (node (ref "U$1") (pin "P$255") (pinfunction "255_P$255") (pintype "bidirectional"))
      (node (ref "U$1") (pin "P$256") (pinfunction "256_P$256") (pintype "bidirectional"))
      (node (ref "U$1") (pin "P$257") (pinfunction "257_P$257") (pintype "bidirectional"))
      (node (ref "U$1") (pin "P$258") (pinfunction "258_P$258") (pintype "bidirectional"))
      (node (ref "U$1") (pin "P$259") (pinfunction "259_P$259") (pintype "bidirectional"))
      (node (ref "U$1") (pin "P$260") (pinfunction "260_P$260") (pintype "bidirectional"))
      (node (ref "U$1") (pin "P$261") (pinfunction "261_P$261") (pintype "bidirectional"))
      (node (ref "U$1") (pin "P$262") (pinfunction "262_P$262") (pintype "bidirectional"))
      (node (ref "U$1") (pin "P$30") (pinfunction "30_P$30") (pintype "bidirectional"))
      (node (ref "U$1") (pin "P$32") (pinfunction "32_P$32") (pintype "bidirectional"))
      (node (ref "U$1") (pin "P$37") (pinfunction "37_P$37") (pintype "bidirectional"))
      (node (ref "U$1") (pin "P$39") (pinfunction "39_P$39") (pintype "bidirectional"))
      (node (ref "U$1") (pin "P$48") (pinfunction "48_P$48") (pintype "bidirectional"))
      (node (ref "U$1") (pin "P$50") (pinfunction "50_P$50") (pintype "bidirectional"))
      (node (ref "U$1") (pin "P$67") (pinfunction "67_P$67") (pintype "bidirectional"))
      (node (ref "U$1") (pin "P$68") (pinfunction "68_P$68") (pintype "bidirectional"))
      (node (ref "U$1") (pin "P$69") (pinfunction "69_P$69") (pintype "bidirectional"))
      (node (ref "U$1") (pin "P$70") (pinfunction "70_P$70") (pintype "bidirectional"))
      (node (ref "U$12") (pin "P$4") (pinfunction "GND_P$4") (pintype "bidirectional"))
      (node (ref "U$14") (pin "C4") (pinfunction "SGND_C4") (pintype "bidirectional"))
      (node (ref "U$14") (pin "G1") (pinfunction "G1_G1") (pintype "bidirectional"))
      (node (ref "U$14") (pin "G2") (pinfunction "G2_G2") (pintype "bidirectional"))
      (node (ref "U$14") (pin "G3") (pinfunction "G3_G3") (pintype "bidirectional"))
      (node (ref "U$14") (pin "G4") (pinfunction "G4_G4") (pintype "bidirectional"))
      (node (ref "U$14") (pin "G5") (pinfunction "G5_G5") (pintype "bidirectional"))
      (node (ref "U$14") (pin "G6") (pinfunction "G6_G6") (pintype "bidirectional"))
      (node (ref "U$14") (pin "G7") (pinfunction "G7_G7") (pintype "bidirectional"))
      (node (ref "U$14") (pin "G8") (pinfunction "G8_G8") (pintype "bidirectional"))
      (node (ref "U$14") (pin "T6") (pinfunction "GND_T6") (pintype "bidirectional"))
      (node (ref "U$15") (pin "3") (pinfunction "3GND_3") (pintype "bidirectional"))
      (node (ref "U1") (pin "11") (pinfunction "GND_11") (pintype "power_in"))
      (node (ref "U2") (pin "4") (pinfunction "GND_4") (pintype "power_in"))
      (node (ref "U201") (pin "11") (pinfunction "GND_11") (pintype "power_in"))
      (node (ref "U3") (pin "11") (pinfunction "GND_11") (pintype "power_in"))
      (node (ref "U5") (pin "4") (pinfunction "GND_4") (pintype "power_in"))
      (node (ref "X1") (pin "GND@1") (pinfunction "GND1_GND@1") (pintype "power_in"))
      (node (ref "X1") (pin "GND@2") (pinfunction "GND2_GND@2") (pintype "power_in"))
      (node (ref "X1") (pin "GND@3") (pinfunction "GND3_GND@3") (pintype "power_in"))
      (node (ref "X1") (pin "GND@4") (pinfunction "GND4_GND@4") (pintype "power_in"))
      (node (ref "X2") (pin "GND@1") (pinfunction "GND1_GND@1") (pintype "power_in"))
      (node (ref "X2") (pin "GND@2") (pinfunction "GND2_GND@2") (pintype "power_in"))
      (node (ref "X2") (pin "GND@3") (pinfunction "GND3_GND@3") (pintype "power_in"))
      (node (ref "X2") (pin "GND@4") (pinfunction "GND4_GND@4") (pintype "power_in"))
      (node (ref "X3") (pin "GND@1") (pinfunction "GND1_GND@1") (pintype "power_in"))
      (node (ref "X3") (pin "GND@2") (pinfunction "GND2_GND@2") (pintype "power_in"))
      (node (ref "X3") (pin "GND@3") (pinfunction "GND3_GND@3") (pintype "power_in"))
      (node (ref "X3") (pin "GND@4") (pinfunction "GND4_GND@4") (pintype "power_in"))
    )
    (net (code "10") (name "Net-(BAT2--)") (class "Default")
      (node (ref "BAT2") (pin "GND") (pinfunction "-_GND") (pintype "power_in"))
      (node (ref "U$1") (pin "P$21") (pinfunction "BAT_RTC_P$21") (pintype "bidirectional"))
    )
    (net (code "11") (name "Net-(CN1-PadD+)") (class "Default")
      (node (ref "CN1") (pin "D+") (pinfunction "D+_D+") (pintype "bidirectional"))
      (node (ref "U$11") (pin "3") (pinfunction "3_3") (pintype "bidirectional"))
    )
    (net (code "12") (name "Net-(CN1-PadD-)") (class "Default")
      (node (ref "CN1") (pin "D-") (pinfunction "D-_D-") (pintype "bidirectional"))
      (node (ref "U$11") (pin "4") (pinfunction "4_4") (pintype "bidirectional"))
    )
    (net (code "13") (name "Net-(D6-Pad-)") (class "Default")
      (node (ref "D6") (pin "-") (pinfunction "-_-") (pintype "passive"))
      (node (ref "R20") (pin "1") (pinfunction "1_1") (pintype "passive"))
    )
    (net (code "14") (name "Net-(D7-Pad-)") (class "Default")
      (node (ref "D7") (pin "-") (pinfunction "-_-") (pintype "passive"))
      (node (ref "R21") (pin "1") (pinfunction "1_1") (pintype "passive"))
    )
    (net (code "15") (name "Net-(D8-PadC)") (class "Default")
      (node (ref "D8") (pin "C") (pinfunction "C_C") (pintype "passive"))
      (node (ref "J201") (pin "1") (pinfunction "1_1") (pintype "passive"))
      (node (ref "L201") (pin "P$2") (pinfunction "P$2_P$2") (pintype "bidirectional"))
    )
    (net (code "16") (name "Net-(D9-PadC)") (class "Default")
      (node (ref "D9") (pin "C") (pinfunction "C_C") (pintype "passive"))
      (node (ref "J5") (pin "1") (pinfunction "1_1") (pintype "passive"))
      (node (ref "L3") (pin "P$2") (pinfunction "P$2_P$2") (pintype "bidirectional"))
    )
    (net (code "17") (name "Net-(D10-PadC)") (class "Default")
      (node (ref "D10") (pin "C") (pinfunction "C_C") (pintype "passive"))
      (node (ref "J1") (pin "1") (pinfunction "1_1") (pintype "passive"))
      (node (ref "L1") (pin "P$2") (pinfunction "P$2_P$2") (pintype "bidirectional"))
    )
    (net (code "18") (name "Net-(D401-PadC)") (class "Default")
      (node (ref "D401") (pin "C") (pinfunction "C_C") (pintype "passive"))
      (node (ref "J401") (pin "1") (pinfunction "1_1") (pintype "passive"))
      (node (ref "L7") (pin "P$2") (pinfunction "P$2_P$2") (pintype "bidirectional"))
    )
    (net (code "19") (name "Net-(JP5-Pad1)") (class "Default")
      (node (ref "JP5") (pin "1") (pinfunction "1_1") (pintype "passive"))
      (node (ref "R1") (pin "2") (pinfunction "2_2") (pintype "passive"))
    )
    (net (code "20") (name "Net-(JP9-Pad1)") (class "Default")
      (node (ref "JP9") (pin "1") (pinfunction "1_1") (pintype "passive"))
      (node (ref "R18") (pin "2") (pinfunction "2_2") (pintype "passive"))
    )
    (net (code "21") (name "Net-(PWR1-Pad+)") (class "Default")
      (node (ref "PWR1") (pin "+") (pinfunction "+_+") (pintype "passive"))
      (node (ref "R25") (pin "1") (pinfunction "1_1") (pintype "passive"))
    )
    (net (code "22") (name "Net-(Q3-B)") (class "Default")
      (node (ref "Q3") (pin "1") (pinfunction "B_1") (pintype "passive"))
      (node (ref "R11") (pin "2") (pinfunction "2_2") (pintype "passive"))
      (node (ref "R15") (pin "1") (pinfunction "1_1") (pintype "passive"))
    )
    (net (code "23") (name "Net-(Q3-C)") (class "Default")
      (node (ref "Q3") (pin "3") (pinfunction "C_3") (pintype "passive"))
      (node (ref "R20") (pin "2") (pinfunction "2_2") (pintype "passive"))
    )
    (net (code "24") (name "Net-(Q4-B)") (class "Default")
      (node (ref "Q4") (pin "1") (pinfunction "B_1") (pintype "passive"))
      (node (ref "R16") (pin "2") (pinfunction "2_2") (pintype "passive"))
      (node (ref "R17") (pin "1") (pinfunction "1_1") (pintype "passive"))
    )
    (net (code "25") (name "Net-(Q4-C)") (class "Default")
      (node (ref "Q4") (pin "3") (pinfunction "C_3") (pintype "passive"))
      (node (ref "R21") (pin "2") (pinfunction "2_2") (pintype "passive"))
    )
    (net (code "26") (name "Net-(R3-2)") (class "Default")
      (node (ref "J5") (pin "3") (pinfunction "3_3") (pintype "passive"))
      (node (ref "R3") (pin "P$2") (pinfunction "2_P$2") (pintype "passive"))
    )
    (net (code "27") (name "Net-(R5-2)") (class "Default")
      (node (ref "J5") (pin "5") (pinfunction "5_5") (pintype "passive"))
      (node (ref "R5") (pin "P$2") (pinfunction "2_P$2") (pintype "passive"))
    )
    (net (code "28") (name "Net-(R7-2)") (class "Default")
      (node (ref "J5") (pin "4") (pinfunction "4_4") (pintype "passive"))
      (node (ref "R7") (pin "P$2") (pinfunction "2_P$2") (pintype "passive"))
    )
    (net (code "29") (name "Net-(R9-2)") (class "Default")
      (node (ref "J5") (pin "2") (pinfunction "2_2") (pintype "passive"))
      (node (ref "R9") (pin "P$2") (pinfunction "2_P$2") (pintype "passive"))
    )
    (net (code "30") (name "Net-(R404-1)") (class "Default")
      (node (ref "R404") (pin "P$1") (pinfunction "1_P$1") (pintype "passive"))
      (node (ref "U1") (pin "20") (pinfunction "B1_20") (pintype "bidirectional"))
    )
    (net (code "31") (name "Net-(R404-2)") (class "Default")
      (node (ref "J401") (pin "2") (pinfunction "2_2") (pintype "passive"))
      (node (ref "JP12") (pin "1") (pinfunction "1_1") (pintype "passive"))
      (node (ref "R404") (pin "P$2") (pinfunction "2_P$2") (pintype "passive"))
    )
    (net (code "32") (name "Net-(R405-1)") (class "Default")
      (node (ref "R405") (pin "P$1") (pinfunction "1_P$1") (pintype "passive"))
      (node (ref "U1") (pin "18") (pinfunction "B2_18") (pintype "bidirectional"))
    )
    (net (code "33") (name "Net-(R405-2)") (class "Default")
      (node (ref "J401") (pin "3") (pinfunction "3_3") (pintype "passive"))
      (node (ref "JP8") (pin "1") (pinfunction "1_1") (pintype "passive"))
      (node (ref "R405") (pin "P$2") (pinfunction "2_P$2") (pintype "passive"))
    )
    (net (code "34") (name "Net-(U$1-ANC0_GPIO28)") (class "Default")
      (node (ref "U$1") (pin "P$153") (pinfunction "ANC0_GPIO28_P$153") (pintype "bidirectional"))
      (node (ref "U3") (pin "6") (pinfunction "A5_6") (pintype "bidirectional"))
    )
    (net (code "35") (name "Net-(U$1-ANC1_GPIO29)") (class "Default")
      (node (ref "U$1") (pin "P$154") (pinfunction "ANC1_GPIO29_P$154") (pintype "bidirectional"))
      (node (ref "U3") (pin "7") (pinfunction "A6_7") (pintype "bidirectional"))
    )
    (net (code "36") (name "Net-(U$1-ANC2_GPIO30)") (class "Default")
      (node (ref "U$1") (pin "P$155") (pinfunction "ANC2_GPIO30_P$155") (pintype "bidirectional"))
      (node (ref "U3") (pin "8") (pinfunction "A7_8") (pintype "bidirectional"))
    )
    (net (code "37") (name "Net-(U$1-ANC3_GPIO31)") (class "Default")
      (node (ref "U$1") (pin "P$156") (pinfunction "ANC3_GPIO31_P$156") (pintype "bidirectional"))
      (node (ref "U3") (pin "9") (pinfunction "A8_9") (pintype "bidirectional"))
    )
    (net (code "38") (name "Net-(U$1-BOOT_TP1)") (class "Default")
      (node (ref "C19") (pin "2") (pinfunction "2_2") (pintype "passive"))
      (node (ref "U$1") (pin "P$47") (pinfunction "BOOT_TP1_P$47") (pintype "bidirectional"))
    )
    (net (code "39") (name "Net-(U$1-GPIO21)") (class "Default")
      (node (ref "U$1") (pin "P$147") (pinfunction "GPIO21_P$147") (pintype "bidirectional"))
      (node (ref "U3") (pin "1") (pinfunction "A1_1") (pintype "bidirectional"))
    )
    (net (code "40") (name "Net-(U$1-GPIO22)") (class "Default")
      (node (ref "U$1") (pin "P$148") (pinfunction "GPIO22_P$148") (pintype "bidirectional"))
      (node (ref "U3") (pin "3") (pinfunction "A2_3") (pintype "bidirectional"))
    )
    (net (code "41") (name "Net-(U$1-GPIO23)") (class "Default")
      (node (ref "U$1") (pin "P$149") (pinfunction "GPIO23_P$149") (pintype "bidirectional"))
      (node (ref "U3") (pin "4") (pinfunction "A3_4") (pintype "bidirectional"))
    )
    (net (code "42") (name "Net-(U$1-GPIO24)") (class "Default")
      (node (ref "U$1") (pin "P$150") (pinfunction "GPIO24_P$150") (pintype "bidirectional"))
      (node (ref "U3") (pin "5") (pinfunction "A4_5") (pintype "bidirectional"))
    )
    (net (code "43") (name "Net-(U$1-GPS_DR_SYNC)") (class "Default")
      (node (ref "C23") (pin "2") (pinfunction "2_2") (pintype "passive"))
      (node (ref "U$1") (pin "P$42") (pinfunction "GPS_DR_SYNC_P$42") (pintype "bidirectional"))
    )
    (net (code "44") (name "Net-(U$1-I2C1_CLK)") (class "Default")
      (node (ref "U$1") (pin "P$1") (pinfunction "I2C1_CLK_P$1") (pintype "bidirectional"))
      (node (ref "U1") (pin "1") (pinfunction "A1_1") (pintype "bidirectional"))
    )
    (net (code "45") (name "Net-(U$1-I2C1_DATA)") (class "Default")
      (node (ref "U$1") (pin "P$66") (pinfunction "I2C1_DATA_P$66") (pintype "bidirectional"))
      (node (ref "U1") (pin "3") (pinfunction "A2_3") (pintype "bidirectional"))
    )
    (net (code "46") (name "Net-(U$1-RF_DIV)") (class "Default")
      (node (ref "D1") (pin "A") (pinfunction "A_A") (pintype "passive"))
      (node (ref "U$1") (pin "P$31") (pinfunction "RF_DIV_P$31") (pintype "bidirectional"))
      (node (ref "X1") (pin "P") (pinfunction "ANT_P") (pintype "bidirectional"))
    )
    (net (code "47") (name "Net-(U$1-RF_GNSS)") (class "Default")
      (node (ref "C2") (pin "1") (pinfunction "1_1") (pintype "passive"))
      (node (ref "U$1") (pin "P$38") (pinfunction "RF_GNSS_P$38") (pintype "bidirectional"))
    )
    (net (code "48") (name "Net-(U$1-RF_MAIN)") (class "Default")
      (node (ref "D3") (pin "A") (pinfunction "A_A") (pintype "passive"))
      (node (ref "U$1") (pin "P$49") (pinfunction "RF_MAIN_P$49") (pintype "bidirectional"))
      (node (ref "X2") (pin "P") (pinfunction "ANT_P") (pintype "bidirectional"))
    )
    (net (code "49") (name "Net-(U$1-SDIO_CLK)") (class "Default")
      (node (ref "U$1") (pin "P$162") (pinfunction "SDIO_CLK_P$162") (pintype "bidirectional"))
      (node (ref "U$14") (pin "T5") (pinfunction "CLK_T5") (pintype "bidirectional"))
      (node (ref "U$15") (pin "2") (pinfunction "C2_2") (pintype "bidirectional"))
    )
    (net (code "50") (name "Net-(U$1-SDIO_CMD)") (class "Default")
      (node (ref "R24") (pin "1") (pinfunction "1_1") (pintype "passive"))
      (node (ref "U$1") (pin "P$161") (pinfunction "SDIO_CMD_P$161") (pintype "bidirectional"))
      (node (ref "U$14") (pin "T3") (pinfunction "CMD_T3") (pintype "bidirectional"))
      (node (ref "U$15") (pin "1") (pinfunction "C1_1") (pintype "bidirectional"))
    )
    (net (code "51") (name "Net-(U$1-SDIO_DATA_0)") (class "Default")
      (node (ref "RPUD0") (pin "1") (pinfunction "1_1") (pintype "passive"))
      (node (ref "U$1") (pin "P$166") (pinfunction "SDIO_DATA_0_P$166") (pintype "bidirectional"))
      (node (ref "U$14") (pin "T7") (pinfunction "D0_T7") (pintype "bidirectional"))
      (node (ref "U$15") (pin "8") (pinfunction "C8_8") (pintype "bidirectional"))
    )
    (net (code "52") (name "Net-(U$1-SDIO_DATA_1)") (class "Default")
      (node (ref "RPUD1") (pin "1") (pinfunction "1_1") (pintype "passive"))
      (node (ref "U$1") (pin "P$165") (pinfunction "SDIO_DATA_1_P$165") (pintype "bidirectional"))
      (node (ref "U$14") (pin "T8") (pinfunction "D1_T8") (pintype "bidirectional"))
      (node (ref "U$15") (pin "6") (pinfunction "C6_6") (pintype "bidirectional"))
    )
    (net (code "53") (name "Net-(U$1-SDIO_DATA_2)") (class "Default")
      (node (ref "RPUD2") (pin "1") (pinfunction "1_1") (pintype "passive"))
      (node (ref "U$1") (pin "P$164") (pinfunction "SDIO_DATA_2_P$164") (pintype "bidirectional"))
      (node (ref "U$14") (pin "T1") (pinfunction "D2_T1") (pintype "bidirectional"))
      (node (ref "U$15") (pin "5") (pinfunction "C5_5") (pintype "bidirectional"))
    )
    (net (code "54") (name "Net-(U$1-SDIO_DATA_3)") (class "Default")
      (node (ref "RPUD3") (pin "1") (pinfunction "1_1") (pintype "passive"))
      (node (ref "U$1") (pin "P$163") (pinfunction "SDIO_DATA_3_P$163") (pintype "bidirectional"))
      (node (ref "U$14") (pin "T2") (pinfunction "D3_T2") (pintype "bidirectional"))
      (node (ref "U$15") (pin "4") (pinfunction "C4_4") (pintype "bidirectional"))
    )
    (net (code "55") (name "Net-(U$1-SPI1_CLK)") (class "Default")
      (node (ref "U$1") (pin "P$53") (pinfunction "SPI1_CLK_P$53") (pintype "bidirectional"))
      (node (ref "U1") (pin "7") (pinfunction "A6_7") (pintype "bidirectional"))
    )
    (net (code "56") (name "Net-(U$1-SPI1_MISO)") (class "Default")
      (node (ref "U$1") (pin "P$52") (pinfunction "SPI1_MISO_P$52") (pintype "bidirectional"))
      (node (ref "U1") (pin "9") (pinfunction "A8_9") (pintype "bidirectional"))
    )
    (net (code "57") (name "Net-(U$1-SPI1_MOSI)") (class "Default")
      (node (ref "U$1") (pin "P$54") (pinfunction "SPI1_MOSI_P$54") (pintype "bidirectional"))
      (node (ref "U1") (pin "6") (pinfunction "A5_6") (pintype "bidirectional"))
    )
    (net (code "58") (name "Net-(U$1-SPI1_MRDY)") (class "Default")
      (node (ref "U$1") (pin "P$51") (pinfunction "SPI1_MRDY_P$51") (pintype "bidirectional"))
      (node (ref "U1") (pin "8") (pinfunction "A7_8") (pintype "bidirectional"))
    )
    (net (code "59") (name "Net-(U$1-TX_ON)") (class "Default")
      (node (ref "R16") (pin "1") (pinfunction "1_1") (pintype "passive"))
      (node (ref "U$1") (pin "P$60") (pinfunction "TX_ON_P$60") (pintype "bidirectional"))
    )
    (net (code "60") (name "Net-(U$1-UART1_CTS)") (class "Default")
      (node (ref "U$1") (pin "P$4") (pinfunction "UART1_CTS_P$4") (pintype "bidirectional"))
      (node (ref "U201") (pin "7") (pinfunction "A6_7") (pintype "bidirectional"))
    )
    (net (code "61") (name "Net-(U$1-UART1_RTS)") (class "Default")
      (node (ref "U$1") (pin "P$3") (pinfunction "UART1_RTS_P$3") (pintype "bidirectional"))
      (node (ref "U201") (pin "8") (pinfunction "A7_8") (pintype "bidirectional"))
    )
    (net (code "62") (name "Net-(U$1-UART1_RX)") (class "Default")
      (node (ref "U$1") (pin "P$6") (pinfunction "UART1_RX_P$6") (pintype "bidirectional"))
      (node (ref "U201") (pin "5") (pinfunction "A4_5") (pintype "bidirectional"))
    )
    (net (code "63") (name "Net-(U$1-UART1_TX)") (class "Default")
      (node (ref "U$1") (pin "P$5") (pinfunction "UART1_TX_P$5") (pintype "bidirectional"))
      (node (ref "U201") (pin "6") (pinfunction "A5_6") (pintype "bidirectional"))
    )
    (net (code "64") (name "Net-(U$1-UART2_RX)") (class "Default")
      (node (ref "U$1") (pin "P$97") (pinfunction "UART2_RX_P$97") (pintype "bidirectional"))
      (node (ref "U201") (pin "4") (pinfunction "A3_4") (pintype "bidirectional"))
    )
    (net (code "65") (name "Net-(U$1-UART2_TX)") (class "Default")
      (node (ref "U$1") (pin "P$96") (pinfunction "UART2_TX_P$96") (pintype "bidirectional"))
      (node (ref "U201") (pin "3") (pinfunction "A2_3") (pintype "bidirectional"))
    )
    (net (code "66") (name "Net-(U$1-USB_D+)") (class "Default")
      (node (ref "U$1") (pin "P$13") (pinfunction "USB_D+_P$13") (pintype "bidirectional"))
      (node (ref "U$11") (pin "2") (pinfunction "2_2") (pintype "bidirectional"))
      (node (ref "U$12") (pin "P$1") (pinfunction "D+_P$1") (pintype "bidirectional"))
    )
    (net (code "67") (name "Net-(U$1-USB_D-)") (class "Default")
      (node (ref "U$1") (pin "P$12") (pinfunction "USB_D-_P$12") (pintype "bidirectional"))
      (node (ref "U$11") (pin "1") (pinfunction "1_1") (pintype "bidirectional"))
      (node (ref "U$12") (pin "P$2") (pinfunction "D-_P$2") (pintype "bidirectional"))
    )
    (net (code "68") (name "Net-(U$1-WWAN_LED_N)") (class "Default")
      (node (ref "R11") (pin "1") (pinfunction "1_1") (pintype "passive"))
      (node (ref "U$1") (pin "P$106") (pinfunction "WWAN_LED_N_P$106") (pintype "bidirectional"))
    )
    (net (code "69") (name "Net-(U$14-VCC)") (class "Default")
      (node (ref "D5") (pin "A") (pinfunction "A_A") (pintype "passive"))
      (node (ref "R24") (pin "2") (pinfunction "2_2") (pintype "passive"))
      (node (ref "RPUD0") (pin "2") (pinfunction "2_2") (pintype "passive"))
      (node (ref "RPUD1") (pin "2") (pinfunction "2_2") (pintype "passive"))
      (node (ref "RPUD2") (pin "2") (pinfunction "2_2") (pintype "passive"))
      (node (ref "RPUD3") (pin "2") (pinfunction "2_2") (pintype "passive"))
      (node (ref "U$14") (pin "T4") (pinfunction "VCC_T4") (pintype "bidirectional"))
      (node (ref "U$15") (pin "7") (pinfunction "7VCC_7") (pintype "bidirectional"))
    )
    (net (code "70") (name "Net-(U1-B3)") (class "Default")
      (node (ref "S2") (pin "2") (pinfunction "2_2") (pintype "passive"))
      (node (ref "U1") (pin "17") (pinfunction "B3_17") (pintype "bidirectional"))
    )
    (net (code "71") (name "Net-(U1-B5)") (class "Default")
      (node (ref "J1") (pin "2") (pinfunction "2_2") (pintype "passive"))
      (node (ref "U1") (pin "15") (pinfunction "B5_15") (pintype "bidirectional"))
    )
    (net (code "72") (name "Net-(U1-B6)") (class "Default")
      (node (ref "J1") (pin "3") (pinfunction "3_3") (pintype "passive"))
      (node (ref "U1") (pin "14") (pinfunction "B6_14") (pintype "bidirectional"))
    )
    (net (code "73") (name "Net-(U1-B7)") (class "Default")
      (node (ref "J1") (pin "4") (pinfunction "4_4") (pintype "passive"))
      (node (ref "U1") (pin "13") (pinfunction "B7_13") (pintype "bidirectional"))
    )
    (net (code "74") (name "Net-(U1-B8)") (class "Default")
      (node (ref "J1") (pin "5") (pinfunction "5_5") (pintype "passive"))
      (node (ref "U1") (pin "12") (pinfunction "B8_12") (pintype "bidirectional"))
    )
    (net (code "75") (name "Net-(U2-EN)") (class "Default")
      (node (ref "R19") (pin "1") (pinfunction "1_1") (pintype "passive"))
      (node (ref "U2") (pin "7") (pinfunction "EN_7") (pintype "input"))
    )
    (net (code "76") (name "Net-(U2-FB)") (class "Default")
      (node (ref "C4") (pin "2") (pinfunction "2_2") (pintype "passive"))
      (node (ref "R23") (pin "1") (pinfunction "1_1") (pintype "passive"))
      (node (ref "R28") (pin "1") (pinfunction "1_1") (pintype "passive"))
      (node (ref "U2") (pin "5") (pinfunction "FB_5") (pintype "input"))
    )
    (net (code "77") (name "Net-(U2-SW)") (class "Default")
      (node (ref "D12") (pin "C") (pinfunction "C_C") (pintype "passive"))
      (node (ref "L9") (pin "1") (pinfunction "1_1") (pintype "passive"))
      (node (ref "U2") (pin "3") (pinfunction "SW_3") (pintype "output"))
    )
    (net (code "78") (name "Net-(U5-EN)") (class "Default")
      (node (ref "R29") (pin "1") (pinfunction "1_1") (pintype "passive"))
      (node (ref "U5") (pin "7") (pinfunction "EN_7") (pintype "input"))
    )
    (net (code "79") (name "Net-(U5-FB)") (class "Default")
      (node (ref "C36") (pin "2") (pinfunction "2_2") (pintype "passive"))
      (node (ref "R30") (pin "1") (pinfunction "1_1") (pintype "passive"))
      (node (ref "R31") (pin "1") (pinfunction "1_1") (pintype "passive"))
      (node (ref "U5") (pin "5") (pinfunction "FB_5") (pintype "input"))
    )
    (net (code "80") (name "Net-(U5-SW)") (class "Default")
      (node (ref "D2") (pin "C") (pinfunction "C_C") (pintype "passive"))
      (node (ref "L4") (pin "1") (pinfunction "1_1") (pintype "passive"))
      (node (ref "U5") (pin "3") (pinfunction "SW_3") (pintype "output"))
    )
    (net (code "81") (name "Net-(U201-B1)") (class "Default")
      (node (ref "JP7") (pin "1") (pinfunction "1_1") (pintype "passive"))
      (node (ref "S1") (pin "1") (pinfunction "1_1") (pintype "passive"))
      (node (ref "U201") (pin "20") (pinfunction "B1_20") (pintype "bidirectional"))
    )
    (net (code "82") (name "Net-(U201-B2)") (class "Default")
      (node (ref "R13") (pin "1") (pinfunction "1_1") (pintype "passive"))
      (node (ref "U201") (pin "18") (pinfunction "B2_18") (pintype "bidirectional"))
    )
    (net (code "83") (name "Net-(U201-B3)") (class "Default")
      (node (ref "R12") (pin "1") (pinfunction "1_1") (pintype "passive"))
      (node (ref "U201") (pin "17") (pinfunction "B3_17") (pintype "bidirectional"))
    )
    (net (code "84") (name "Net-(U201-B4)") (class "Default")
      (node (ref "R22") (pin "1") (pinfunction "1_1") (pintype "passive"))
      (node (ref "U201") (pin "16") (pinfunction "B4_16") (pintype "bidirectional"))
    )
    (net (code "85") (name "Net-(U201-B5)") (class "Default")
      (node (ref "R14") (pin "1") (pinfunction "1_1") (pintype "passive"))
      (node (ref "U201") (pin "15") (pinfunction "B5_15") (pintype "bidirectional"))
    )
    (net (code "86") (name "Net-(U201-B7)") (class "Default")
      (node (ref "R1") (pin "1") (pinfunction "1_1") (pintype "passive"))
      (node (ref "U201") (pin "13") (pinfunction "B7_13") (pintype "bidirectional"))
    )
    (net (code "87") (name "Net-(U201-B8)") (class "Default")
      (node (ref "R18") (pin "1") (pinfunction "1_1") (pintype "passive"))
      (node (ref "U201") (pin "12") (pinfunction "B8_12") (pintype "bidirectional"))
    )
    (net (code "88") (name "Net-(X3-ANT)") (class "Default")
      (node (ref "C2") (pin "2") (pinfunction "2_2") (pintype "passive"))
      (node (ref "D201") (pin "A") (pinfunction "A_A") (pintype "passive"))
      (node (ref "L5") (pin "2") (pinfunction "2_2") (pintype "passive"))
      (node (ref "X3") (pin "P") (pinfunction "ANT_P") (pintype "bidirectional"))
    )
    (net (code "89") (name "POWER_SW") (class "Default")
      (node (ref "C34") (pin "2") (pinfunction "2_2") (pintype "passive"))
      (node (ref "U$1") (pin "P$59") (pinfunction "POWER_ON_N_P$59") (pintype "bidirectional"))
      (node (ref "U1") (pin "4") (pinfunction "A3_4") (pintype "bidirectional"))
    )
    (net (code "90") (name "RESET") (class "Default")
      (node (ref "C33") (pin "2") (pinfunction "2_2") (pintype "passive"))
      (node (ref "U$1") (pin "P$11") (pinfunction "RESET_IN_N_P$11") (pintype "bidirectional"))
      (node (ref "U201") (pin "1") (pinfunction "A1_1") (pintype "bidirectional"))
    )
    (net (code "91") (name "SD_DETECT") (class "Default")
      (node (ref "C21") (pin "1") (pinfunction "1_1") (pintype "passive"))
      (node (ref "U$1") (pin "P$109") (pinfunction "GPIO42_P$109") (pintype "bidirectional"))
      (node (ref "U$14") (pin "SW") (pinfunction "SW_SW") (pintype "bidirectional"))
    )
    (net (code "92") (name "SERIAL1_CTS") (class "Default")
      (node (ref "J201") (pin "3") (pinfunction "3_3") (pintype "passive"))
      (node (ref "R12") (pin "2") (pinfunction "2_2") (pintype "passive"))
    )
    (net (code "93") (name "SERIAL1_RTS") (class "Default")
      (node (ref "J201") (pin "2") (pinfunction "2_2") (pintype "passive"))
      (node (ref "R13") (pin "2") (pinfunction "2_2") (pintype "passive"))
    )
    (net (code "94") (name "SERIAL1_RX") (class "Default")
      (node (ref "J201") (pin "5") (pinfunction "5_5") (pintype "passive"))
      (node (ref "R14") (pin "2") (pinfunction "2_2") (pintype "passive"))
    )
    (net (code "95") (name "SERIAL1_TX") (class "Default")
      (node (ref "J201") (pin "4") (pinfunction "4_4") (pintype "passive"))
      (node (ref "R22") (pin "2") (pinfunction "2_2") (pintype "passive"))
    )
    (net (code "96") (name "SIM_CLK") (class "Default")
      (node (ref "D4") (pin "5") (pinfunction "C4_5") (pintype "passive"))
      (node (ref "U$1") (pin "P$27") (pinfunction "UIM1_CLK_P$27") (pintype "bidirectional"))
      (node (ref "U$14") (pin "C3") (pinfunction "SCLK_C3") (pintype "bidirectional"))
    )
    (net (code "97") (name "SIM_DATA") (class "Default")
      (node (ref "D4") (pin "4") (pinfunction "C3_4") (pintype "passive"))
      (node (ref "R2") (pin "2") (pinfunction "2_2") (pintype "passive"))
      (node (ref "U$1") (pin "P$28") (pinfunction "UIM1_DATA_P$28") (pintype "bidirectional"))
      (node (ref "U$14") (pin "C6") (pinfunction "DATA_C6") (pintype "bidirectional"))
    )
    (net (code "98") (name "SIM_DETECT") (class "Default")
      (node (ref "D4") (pin "1") (pinfunction "C1_1") (pintype "passive"))
      (node (ref "U$1") (pin "P$64") (pinfunction "UIM1_DET_P$64") (pintype "bidirectional"))
    )
    (net (code "99") (name "SIM_RST") (class "Default")
      (node (ref "D4") (pin "3") (pinfunction "C2_3") (pintype "passive"))
      (node (ref "U$1") (pin "P$29") (pinfunction "UIM1_RESET_N_P$29") (pintype "bidirectional"))
      (node (ref "U$14") (pin "C2") (pinfunction "RST_C2") (pintype "bidirectional"))
    )
    (net (code "100") (name "USB_VBUS") (class "Default")
      (node (ref "C11") (pin "2") (pinfunction "2_2") (pintype "passive"))
      (node (ref "CN1") (pin "VBUS") (pinfunction "VBUS_VBUS") (pintype "power_in"))
      (node (ref "U$12") (pin "P$6") (pinfunction "VBUS_P$6") (pintype "bidirectional"))
    )
    (net (code "101") (name "W_DISABLE") (class "Default")
      (node (ref "C35") (pin "2") (pinfunction "2_2") (pintype "passive"))
      (node (ref "U$1") (pin "P$151") (pinfunction "W_DISABLE_N_P$151") (pintype "bidirectional"))
      (node (ref "U1") (pin "5") (pinfunction "A4_5") (pintype "bidirectional"))
    )
    (net (code "102") (name "unconnected-(CN1-PadID)") (class "Default")
      (node (ref "CN1") (pin "ID") (pinfunction "ID_ID") (pintype "bidirectional"))
    )
    (net (code "103") (name "unconnected-(U$1-CX1_GPIO34-PadP$100)") (class "Default")
      (node (ref "U$1") (pin "P$100") (pinfunction "CX1_GPIO34_P$100") (pintype "bidirectional"))
    )
    (net (code "104") (name "unconnected-(U$1-CX2_GPIO35-PadP$101)") (class "Default")
      (node (ref "U$1") (pin "P$101") (pinfunction "CX2_GPIO35_P$101") (pintype "bidirectional"))
    )
    (net (code "105") (name "unconnected-(U$1-CX3_GPIO36-PadP$102)") (class "Default")
      (node (ref "U$1") (pin "P$102") (pinfunction "CX3_GPIO36_P$102") (pintype "bidirectional"))
    )
    (net (code "106") (name "unconnected-(U$1-GPIO2-PadP$10)") (class "Default")
      (node (ref "U$1") (pin "P$10") (pinfunction "GPIO2_P$10") (pintype "bidirectional"))
    )
    (net (code "107") (name "unconnected-(U$1-GPIO7-PadP$40)") (class "Default")
      (node (ref "U$1") (pin "P$40") (pinfunction "GPIO7_P$40") (pintype "bidirectional"))
    )
    (net (code "108") (name "unconnected-(U$1-GPIO8-PadP$41)") (class "Default")
      (node (ref "U$1") (pin "P$41") (pinfunction "GPIO8_P$41") (pintype "bidirectional"))
    )
    (net (code "109") (name "unconnected-(U$1-GPIO13-PadP$44)") (class "Default")
      (node (ref "U$1") (pin "P$44") (pinfunction "GPIO13_P$44") (pintype "bidirectional"))
    )
    (net (code "110") (name "unconnected-(U$1-GPIO25-PadP$159)") (class "Default")
      (node (ref "U$1") (pin "P$159") (pinfunction "GPIO25_P$159") (pintype "bidirectional"))
    )
    (net (code "111") (name "unconnected-(U$1-GPIO32-PadP$104)") (class "Default")
      (node (ref "U$1") (pin "P$104") (pinfunction "GPIO32_P$104") (pintype "bidirectional"))
    )
    (net (code "112") (name "unconnected-(U$1-GPIO33-PadP$105)") (class "Default")
      (node (ref "U$1") (pin "P$105") (pinfunction "GPIO33_P$105") (pintype "bidirectional"))
    )
    (net (code "113") (name "unconnected-(U$1-GPIO37-PadP$103)") (class "Default")
      (node (ref "U$1") (pin "P$103") (pinfunction "GPIO37_P$103") (pintype "bidirectional"))
    )
    (net (code "114") (name "unconnected-(U$1-GPIO38-PadP$92)") (class "Default")
      (node (ref "U$1") (pin "P$92") (pinfunction "GPIO38_P$92") (pintype "bidirectional"))
    )
    (net (code "115") (name "unconnected-(U$1-GPIO39-PadP$93)") (class "Default")
      (node (ref "U$1") (pin "P$93") (pinfunction "GPIO39_P$93") (pintype "bidirectional"))
    )
    (net (code "116") (name "unconnected-(U$1-GPIO40-PadP$94)") (class "Default")
      (node (ref "U$1") (pin "P$94") (pinfunction "GPIO40_P$94") (pintype "bidirectional"))
    )
    (net (code "117") (name "unconnected-(U$1-GPIO41-PadP$95)") (class "Default")
      (node (ref "U$1") (pin "P$95") (pinfunction "GPIO41_P$95") (pintype "bidirectional"))
    )
    (net (code "118") (name "unconnected-(U$1-HSIC_DATA-PadP$14)") (class "Default")
      (node (ref "U$1") (pin "P$14") (pinfunction "HSIC_DATA_P$14") (pintype "bidirectional"))
    )
    (net (code "119") (name "unconnected-(U$1-HSIC_STRB-PadP$15)") (class "Default")
      (node (ref "U$1") (pin "P$15") (pinfunction "HSIC_STRB_P$15") (pintype "bidirectional"))
    )
    (net (code "120") (name "unconnected-(U$1-PCM,I2S_CLK-PadP$36)") (class "Default")
      (node (ref "U$1") (pin "P$36") (pinfunction "PCM,I2S_CLK_P$36") (pintype "bidirectional"))
    )
    (net (code "121") (name "unconnected-(U$1-PCM,I2S_IN-PadP$34)") (class "Default")
      (node (ref "U$1") (pin "P$34") (pinfunction "PCM,I2S_IN_P$34") (pintype "bidirectional"))
    )
    (net (code "122") (name "unconnected-(U$1-PCM,I2S_OUT-PadP$33)") (class "Default")
      (node (ref "U$1") (pin "P$33") (pinfunction "PCM,I2S_OUT_P$33") (pintype "bidirectional"))
    )
    (net (code "123") (name "unconnected-(U$1-PCM,I2S_SYNC-PadP$35)") (class "Default")
      (node (ref "U$1") (pin "P$35") (pinfunction "PCM,I2S_SYNC_P$35") (pintype "bidirectional"))
    )
    (net (code "124") (name "unconnected-(U$1-R17-PadP$17)") (class "Default")
      (node (ref "U$1") (pin "P$17") (pinfunction "R17_P$17") (pintype "bidirectional"))
    )
    (net (code "125") (name "unconnected-(U$1-R18-PadP$18)") (class "Default")
      (node (ref "U$1") (pin "P$18") (pinfunction "R18_P$18") (pintype "bidirectional"))
    )
    (net (code "126") (name "unconnected-(U$1-R19-PadP$19)") (class "Default")
      (node (ref "U$1") (pin "P$19") (pinfunction "R19_P$19") (pintype "bidirectional"))
    )
    (net (code "127") (name "unconnected-(U$1-R20-PadP$20)") (class "Default")
      (node (ref "U$1") (pin "P$20") (pinfunction "R20_P$20") (pintype "bidirectional"))
    )
    (net (code "128") (name "unconnected-(U$1-R43-PadP$43)") (class "Default")
      (node (ref "U$1") (pin "P$43") (pinfunction "R43_P$43") (pintype "bidirectional"))
    )
    (net (code "129") (name "unconnected-(U$1-R71-PadP$71)") (class "Default")
      (node (ref "U$1") (pin "P$71") (pinfunction "R71_P$71") (pintype "bidirectional"))
    )
    (net (code "130") (name "unconnected-(U$1-R72-PadP$72)") (class "Default")
      (node (ref "U$1") (pin "P$72") (pinfunction "R72_P$72") (pintype "bidirectional"))
    )
    (net (code "131") (name "unconnected-(U$1-R73-PadP$73)") (class "Default")
      (node (ref "U$1") (pin "P$73") (pinfunction "R73_P$73") (pintype "bidirectional"))
    )
    (net (code "132") (name "unconnected-(U$1-R74-PadP$74)") (class "Default")
      (node (ref "U$1") (pin "P$74") (pinfunction "R74_P$74") (pintype "bidirectional"))
    )
    (net (code "133") (name "unconnected-(U$1-R75-PadP$75)") (class "Default")
      (node (ref "U$1") (pin "P$75") (pinfunction "R75_P$75") (pintype "bidirectional"))
    )
    (net (code "134") (name "unconnected-(U$1-R76-PadP$76)") (class "Default")
      (node (ref "U$1") (pin "P$76") (pinfunction "R76_P$76") (pintype "bidirectional"))
    )
    (net (code "135") (name "unconnected-(U$1-R77-PadP$77)") (class "Default")
      (node (ref "U$1") (pin "P$77") (pinfunction "R77_P$77") (pintype "bidirectional"))
    )
    (net (code "136") (name "unconnected-(U$1-R78-PadP$78)") (class "Default")
      (node (ref "U$1") (pin "P$78") (pinfunction "R78_P$78") (pintype "bidirectional"))
    )
    (net (code "137") (name "unconnected-(U$1-R79-PadP$79)") (class "Default")
      (node (ref "U$1") (pin "P$79") (pinfunction "R79_P$79") (pintype "bidirectional"))
    )
    (net (code "138") (name "unconnected-(U$1-R80-PadP$80)") (class "Default")
      (node (ref "U$1") (pin "P$80") (pinfunction "R80_P$80") (pintype "bidirectional"))
    )
    (net (code "139") (name "unconnected-(U$1-R81-PadP$81)") (class "Default")
      (node (ref "U$1") (pin "P$81") (pinfunction "R81_P$81") (pintype "bidirectional"))
    )
    (net (code "140") (name "unconnected-(U$1-R82-PadP$82)") (class "Default")
      (node (ref "U$1") (pin "P$82") (pinfunction "R82_P$82") (pintype "bidirectional"))
    )
    (net (code "141") (name "unconnected-(U$1-R83-PadP$83)") (class "Default")
      (node (ref "U$1") (pin "P$83") (pinfunction "R83_P$83") (pintype "bidirectional"))
    )
    (net (code "142") (name "unconnected-(U$1-R84-PadP$84)") (class "Default")
      (node (ref "U$1") (pin "P$84") (pinfunction "R84_P$84") (pintype "bidirectional"))
    )
    (net (code "143") (name "unconnected-(U$1-R85-PadP$85)") (class "Default")
      (node (ref "U$1") (pin "P$85") (pinfunction "R85_P$85") (pintype "bidirectional"))
    )
    (net (code "144") (name "unconnected-(U$1-R86-PadP$86)") (class "Default")
      (node (ref "U$1") (pin "P$86") (pinfunction "R86_P$86") (pintype "bidirectional"))
    )
    (net (code "145") (name "unconnected-(U$1-R87-PadP$87)") (class "Default")
      (node (ref "U$1") (pin "P$87") (pinfunction "R87_P$87") (pintype "bidirectional"))
    )
    (net (code "146") (name "unconnected-(U$1-R88-PadP$88)") (class "Default")
      (node (ref "U$1") (pin "P$88") (pinfunction "R88_P$88") (pintype "bidirectional"))
    )
    (net (code "147") (name "unconnected-(U$1-R89-PadP$89)") (class "Default")
      (node (ref "U$1") (pin "P$89") (pinfunction "R89_P$89") (pintype "bidirectional"))
    )
    (net (code "148") (name "unconnected-(U$1-R90-PadP$90)") (class "Default")
      (node (ref "U$1") (pin "P$90") (pinfunction "R90_P$90") (pintype "bidirectional"))
    )
    (net (code "149") (name "unconnected-(U$1-R98-PadP$98)") (class "Default")
      (node (ref "U$1") (pin "P$98") (pinfunction "R98_P$98") (pintype "bidirectional"))
    )
    (net (code "150") (name "unconnected-(U$1-R99-PadP$99)") (class "Default")
      (node (ref "U$1") (pin "P$99") (pinfunction "R99_P$99") (pintype "bidirectional"))
    )
    (net (code "151") (name "unconnected-(U$1-R114-PadP$114)") (class "Default")
      (node (ref "U$1") (pin "P$114") (pinfunction "R114_P$114") (pintype "bidirectional"))
    )
    (net (code "152") (name "unconnected-(U$1-R115-PadP$115)") (class "Default")
      (node (ref "U$1") (pin "P$115") (pinfunction "R115_P$115") (pintype "bidirectional"))
    )
    (net (code "153") (name "unconnected-(U$1-R116-PadP$116)") (class "Default")
      (node (ref "U$1") (pin "P$116") (pinfunction "R116_P$116") (pintype "bidirectional"))
    )
    (net (code "154") (name "unconnected-(U$1-R117-PadP$117)") (class "Default")
      (node (ref "U$1") (pin "P$117") (pinfunction "R117_P$117") (pintype "bidirectional"))
    )
    (net (code "155") (name "unconnected-(U$1-R118-PadP$118)") (class "Default")
      (node (ref "U$1") (pin "P$118") (pinfunction "R118_P$118") (pintype "bidirectional"))
    )
    (net (code "156") (name "unconnected-(U$1-R119-PadP$119)") (class "Default")
      (node (ref "U$1") (pin "P$119") (pinfunction "R119_P$119") (pintype "bidirectional"))
    )
    (net (code "157") (name "unconnected-(U$1-R120-PadP$120)") (class "Default")
      (node (ref "U$1") (pin "P$120") (pinfunction "R120_P$120") (pintype "bidirectional"))
    )
    (net (code "158") (name "unconnected-(U$1-R121-PadP$121)") (class "Default")
      (node (ref "U$1") (pin "P$121") (pinfunction "R121_P$121") (pintype "bidirectional"))
    )
    (net (code "159") (name "unconnected-(U$1-R122-PadP$122)") (class "Default")
      (node (ref "U$1") (pin "P$122") (pinfunction "R122_P$122") (pintype "bidirectional"))
    )
    (net (code "160") (name "unconnected-(U$1-R123-PadP$123)") (class "Default")
      (node (ref "U$1") (pin "P$123") (pinfunction "R123_P$123") (pintype "bidirectional"))
    )
    (net (code "161") (name "unconnected-(U$1-R124-PadP$124)") (class "Default")
      (node (ref "U$1") (pin "P$124") (pinfunction "R124_P$124") (pintype "bidirectional"))
    )
    (net (code "162") (name "unconnected-(U$1-R129-PadP$129)") (class "Default")
      (node (ref "U$1") (pin "P$129") (pinfunction "R129_P$129") (pintype "bidirectional"))
    )
    (net (code "163") (name "unconnected-(U$1-R130-PadP$130)") (class "Default")
      (node (ref "U$1") (pin "P$130") (pinfunction "R130_P$130") (pintype "bidirectional"))
    )
    (net (code "164") (name "unconnected-(U$1-R131-PadP$131)") (class "Default")
      (node (ref "U$1") (pin "P$131") (pinfunction "R131_P$131") (pintype "bidirectional"))
    )
    (net (code "165") (name "unconnected-(U$1-R132-PadP$132)") (class "Default")
      (node (ref "U$1") (pin "P$132") (pinfunction "R132_P$132") (pintype "bidirectional"))
    )
    (net (code "166") (name "unconnected-(U$1-R133-PadP$133)") (class "Default")
      (node (ref "U$1") (pin "P$133") (pinfunction "R133_P$133") (pintype "bidirectional"))
    )
    (net (code "167") (name "unconnected-(U$1-R134-PadP$134)") (class "Default")
      (node (ref "U$1") (pin "P$134") (pinfunction "R134_P$134") (pintype "bidirectional"))
    )
    (net (code "168") (name "unconnected-(U$1-R135-PadP$135)") (class "Default")
      (node (ref "U$1") (pin "P$135") (pinfunction "R135_P$135") (pintype "bidirectional"))
    )
    (net (code "169") (name "unconnected-(U$1-R140-PadP$140)") (class "Default")
      (node (ref "U$1") (pin "P$140") (pinfunction "R140_P$140") (pintype "bidirectional"))
    )
    (net (code "170") (name "unconnected-(U$1-R141-PadP$141)") (class "Default")
      (node (ref "U$1") (pin "P$141") (pinfunction "R141_P$141") (pintype "bidirectional"))
    )
    (net (code "171") (name "unconnected-(U$1-R142-PadP$142)") (class "Default")
      (node (ref "U$1") (pin "P$142") (pinfunction "R142_P$142") (pintype "bidirectional"))
    )
    (net (code "172") (name "unconnected-(U$1-R143-PadP$143)") (class "Default")
      (node (ref "U$1") (pin "P$143") (pinfunction "R143_P$143") (pintype "bidirectional"))
    )
    (net (code "173") (name "unconnected-(U$1-R144-PadP$144)") (class "Default")
      (node (ref "U$1") (pin "P$144") (pinfunction "R144_P$144") (pintype "bidirectional"))
    )
    (net (code "174") (name "unconnected-(U$1-R145-PadP$145)") (class "Default")
      (node (ref "U$1") (pin "P$145") (pinfunction "R145_P$145") (pintype "bidirectional"))
    )
    (net (code "175") (name "unconnected-(U$1-R146-PadP$146)") (class "Default")
      (node (ref "U$1") (pin "P$146") (pinfunction "R146_P$146") (pintype "bidirectional"))
    )
    (net (code "176") (name "unconnected-(U$1-R160-PadP$160)") (class "Default")
      (node (ref "U$1") (pin "P$160") (pinfunction "R160_P$160") (pintype "bidirectional"))
    )
    (net (code "177") (name "unconnected-(U$1-RESET_OUT_N-PadP$46)") (class "Default")
      (node (ref "U$1") (pin "P$46") (pinfunction "RESET_OUT_N_P$46") (pintype "bidirectional"))
    )
    (net (code "178") (name "unconnected-(U$1-SAFE_PWR_REMOVE-PadP$152)") (class "Default")
      (node (ref "U$1") (pin "P$152") (pinfunction "SAFE_PWR_REMOVE_P$152") (pintype "bidirectional"))
    )
    (net (code "179") (name "unconnected-(U$1-SLEEP_CLK-PadP$23)") (class "Default")
      (node (ref "U$1") (pin "P$23") (pinfunction "SLEEP_CLK_P$23") (pintype "bidirectional"))
    )
    (net (code "180") (name "unconnected-(U$1-SYS_CLK-PadP$22)") (class "Default")
      (node (ref "U$1") (pin "P$22") (pinfunction "SYS_CLK_P$22") (pintype "bidirectional"))
    )
    (net (code "181") (name "unconnected-(U$1-T240-PadP$240)") (class "Default")
      (node (ref "U$1") (pin "P$240") (pinfunction "T240_P$240") (pintype "bidirectional"))
    )
    (net (code "182") (name "unconnected-(U$1-T241-PadP$241)") (class "Default")
      (node (ref "U$1") (pin "P$241") (pinfunction "T241_P$241") (pintype "bidirectional"))
    )
    (net (code "183") (name "unconnected-(U$1-UART1_DCD-PadP$8)") (class "Default")
      (node (ref "U$1") (pin "P$8") (pinfunction "UART1_DCD_P$8") (pintype "bidirectional"))
    )
    (net (code "184") (name "unconnected-(U$1-UART1_DSR-PadP$9)") (class "Default")
      (node (ref "U$1") (pin "P$9") (pinfunction "UART1_DSR_P$9") (pintype "bidirectional"))
    )
    (net (code "185") (name "unconnected-(U$1-UART1_DTR-PadP$7)") (class "Default")
      (node (ref "U$1") (pin "P$7") (pinfunction "UART1_DTR_P$7") (pintype "bidirectional"))
    )
    (net (code "186") (name "unconnected-(U$1-UART1_RI-PadP$2)") (class "Default")
      (node (ref "U$1") (pin "P$2") (pinfunction "UART1_RI_P$2") (pintype "bidirectional"))
    )
    (net (code "187") (name "unconnected-(U$1-UIM2_CLK-PadP$58)") (class "Default")
      (node (ref "U$1") (pin "P$58") (pinfunction "UIM2_CLK_P$58") (pintype "bidirectional"))
    )
    (net (code "188") (name "unconnected-(U$1-UIM2_DATA-PadP$56)") (class "Default")
      (node (ref "U$1") (pin "P$56") (pinfunction "UIM2_DATA_P$56") (pintype "bidirectional"))
    )
    (net (code "189") (name "unconnected-(U$1-UIM2_DET-PadP$65)") (class "Default")
      (node (ref "U$1") (pin "P$65") (pinfunction "UIM2_DET_P$65") (pintype "bidirectional"))
    )
    (net (code "190") (name "unconnected-(U$1-UIM2_RESET_N-PadP$57)") (class "Default")
      (node (ref "U$1") (pin "P$57") (pinfunction "UIM2_RESET_N_P$57") (pintype "bidirectional"))
    )
    (net (code "191") (name "unconnected-(U$1-UIM2_VCC-PadP$55)") (class "Default")
      (node (ref "U$1") (pin "P$55") (pinfunction "UIM2_VCC_P$55") (pintype "bidirectional"))
    )
    (net (code "192") (name "unconnected-(U$1-USB_ID-PadP$91)") (class "Default")
      (node (ref "U$1") (pin "P$91") (pinfunction "USB_ID_P$91") (pintype "bidirectional"))
    )
    (net (code "193") (name "unconnected-(U$1-USB_VBUS-PadP$16)") (class "Default")
      (node (ref "U$1") (pin "P$16") (pinfunction "USB_VBUS_P$16") (pintype "bidirectional"))
    )
    (net (code "194") (name "unconnected-(U$1-WAKE_ON_WWAN-PadP$110)") (class "Default")
      (node (ref "U$1") (pin "P$110") (pinfunction "WAKE_ON_WWAN_P$110") (pintype "bidirectional"))
    )
    (net (code "195") (name "unconnected-(U$12-ID-PadP$3)") (class "Default")
      (node (ref "U$12") (pin "P$3") (pinfunction "ID_P$3") (pintype "bidirectional"))
    )
    (net (code "196") (name "unconnected-(U$12-NC-PadP$5)") (class "Default")
      (node (ref "U$12") (pin "P$5") (pinfunction "NC_P$5") (pintype "bidirectional"))
    )
    (net (code "197") (name "unconnected-(U$14-VPP-PadC5)") (class "Default")
      (node (ref "U$14") (pin "C5") (pinfunction "VPP_C5") (pintype "bidirectional"))
    )
    (net (code "198") (name "unconnected-(U1-B4-Pad16)") (class "Default")
      (node (ref "U1") (pin "16") (pinfunction "B4_16") (pintype "bidirectional"))
    )
    (net (code "199") (name "unconnected-(U2-NC-Pad1)") (class "Default")
      (node (ref "U2") (pin "1") (pinfunction "NC_1") (pintype "no_connect"))
    )
    (net (code "200") (name "unconnected-(U2-NC-Pad6)") (class "Default")
      (node (ref "U2") (pin "6") (pinfunction "NC_6") (pintype "no_connect"))
    )
    (net (code "201") (name "unconnected-(U2-NC-Pad8)") (class "Default")
      (node (ref "U2") (pin "8") (pinfunction "NC_8") (pintype "no_connect"))
    )
    (net (code "202") (name "unconnected-(U3-B1-Pad20)") (class "Default")
      (node (ref "U3") (pin "20") (pinfunction "B1_20") (pintype "bidirectional"))
    )
    (net (code "203") (name "unconnected-(U3-B2-Pad18)") (class "Default")
      (node (ref "U3") (pin "18") (pinfunction "B2_18") (pintype "bidirectional"))
    )
    (net (code "204") (name "unconnected-(U3-B3-Pad17)") (class "Default")
      (node (ref "U3") (pin "17") (pinfunction "B3_17") (pintype "bidirectional"))
    )
    (net (code "205") (name "unconnected-(U3-B4-Pad16)") (class "Default")
      (node (ref "U3") (pin "16") (pinfunction "B4_16") (pintype "bidirectional"))
    )
    (net (code "206") (name "unconnected-(U3-B5-Pad15)") (class "Default")
      (node (ref "U3") (pin "15") (pinfunction "B5_15") (pintype "bidirectional"))
    )
    (net (code "207") (name "unconnected-(U3-B6-Pad14)") (class "Default")
      (node (ref "U3") (pin "14") (pinfunction "B6_14") (pintype "bidirectional"))
    )
    (net (code "208") (name "unconnected-(U3-B7-Pad13)") (class "Default")
      (node (ref "U3") (pin "13") (pinfunction "B7_13") (pintype "bidirectional"))
    )
    (net (code "209") (name "unconnected-(U3-B8-Pad12)") (class "Default")
      (node (ref "U3") (pin "12") (pinfunction "B8_12") (pintype "bidirectional"))
    )
    (net (code "210") (name "unconnected-(U5-NC-Pad1)") (class "Default")
      (node (ref "U5") (pin "1") (pinfunction "NC_1") (pintype "no_connect"))
    )
    (net (code "211") (name "unconnected-(U5-NC-Pad6)") (class "Default")
      (node (ref "U5") (pin "6") (pinfunction "NC_6") (pintype "no_connect"))
    )
    (net (code "212") (name "unconnected-(U5-NC-Pad8)") (class "Default")
      (node (ref "U5") (pin "8") (pinfunction "NC_8") (pintype "no_connect"))
    )
    (net (code "213") (name "unconnected-(U201-A8-Pad9)") (class "Default")
      (node (ref "U201") (pin "9") (pinfunction "A8_9") (pintype "bidirectional"))
    )
    (net (code "214") (name "unconnected-(U201-B6-Pad14)") (class "Default")
      (node (ref "U201") (pin "14") (pinfunction "B6_14") (pintype "bidirectional"))
    )
  )
)
